# FMC_HPC2.net
KiCad netlist of a schematic drawn in Altium Designer
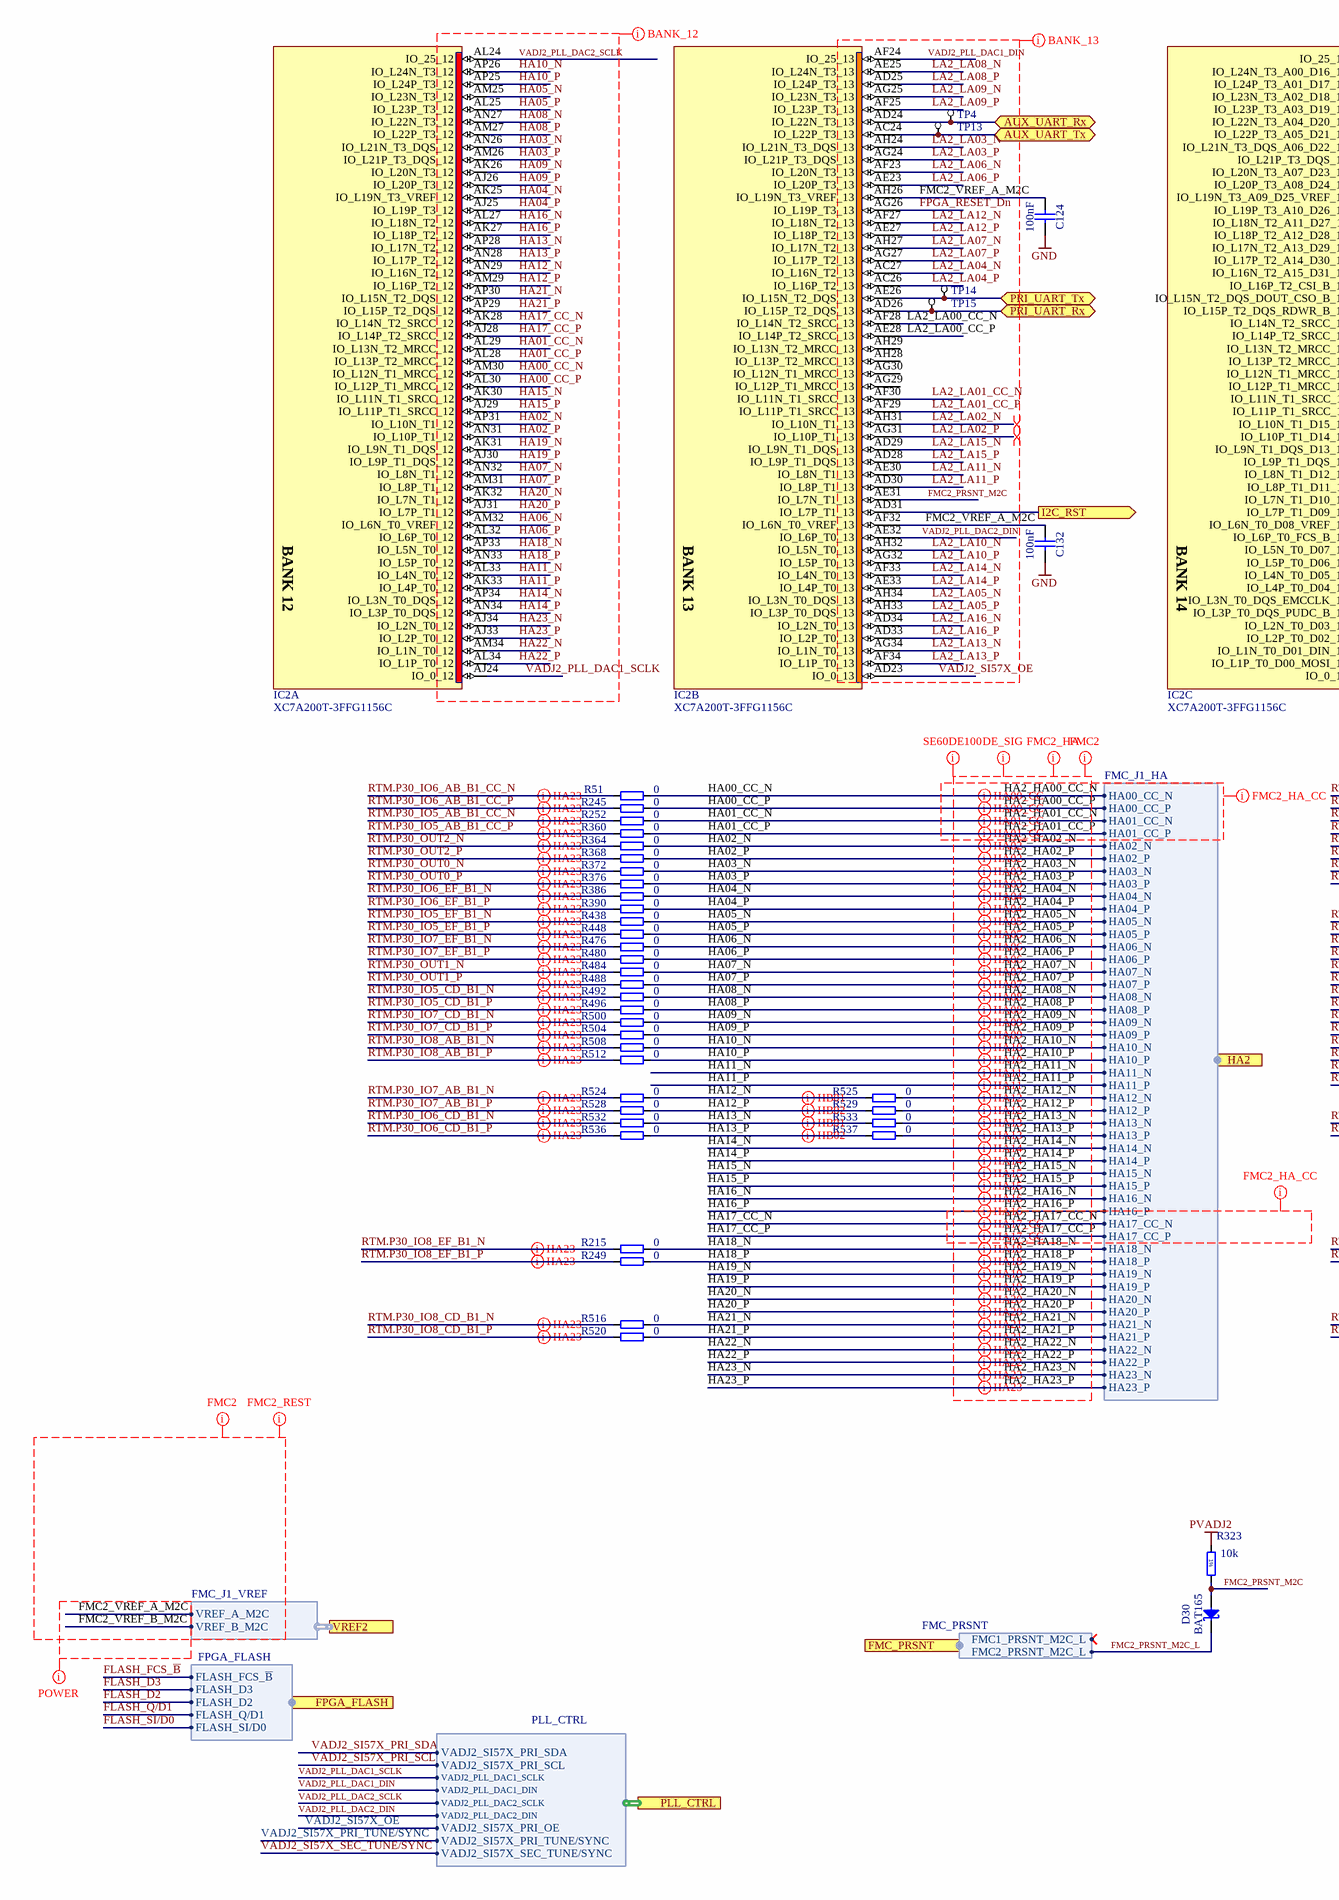
[diagram p0: FMC_HPC2.SchDoc, left]
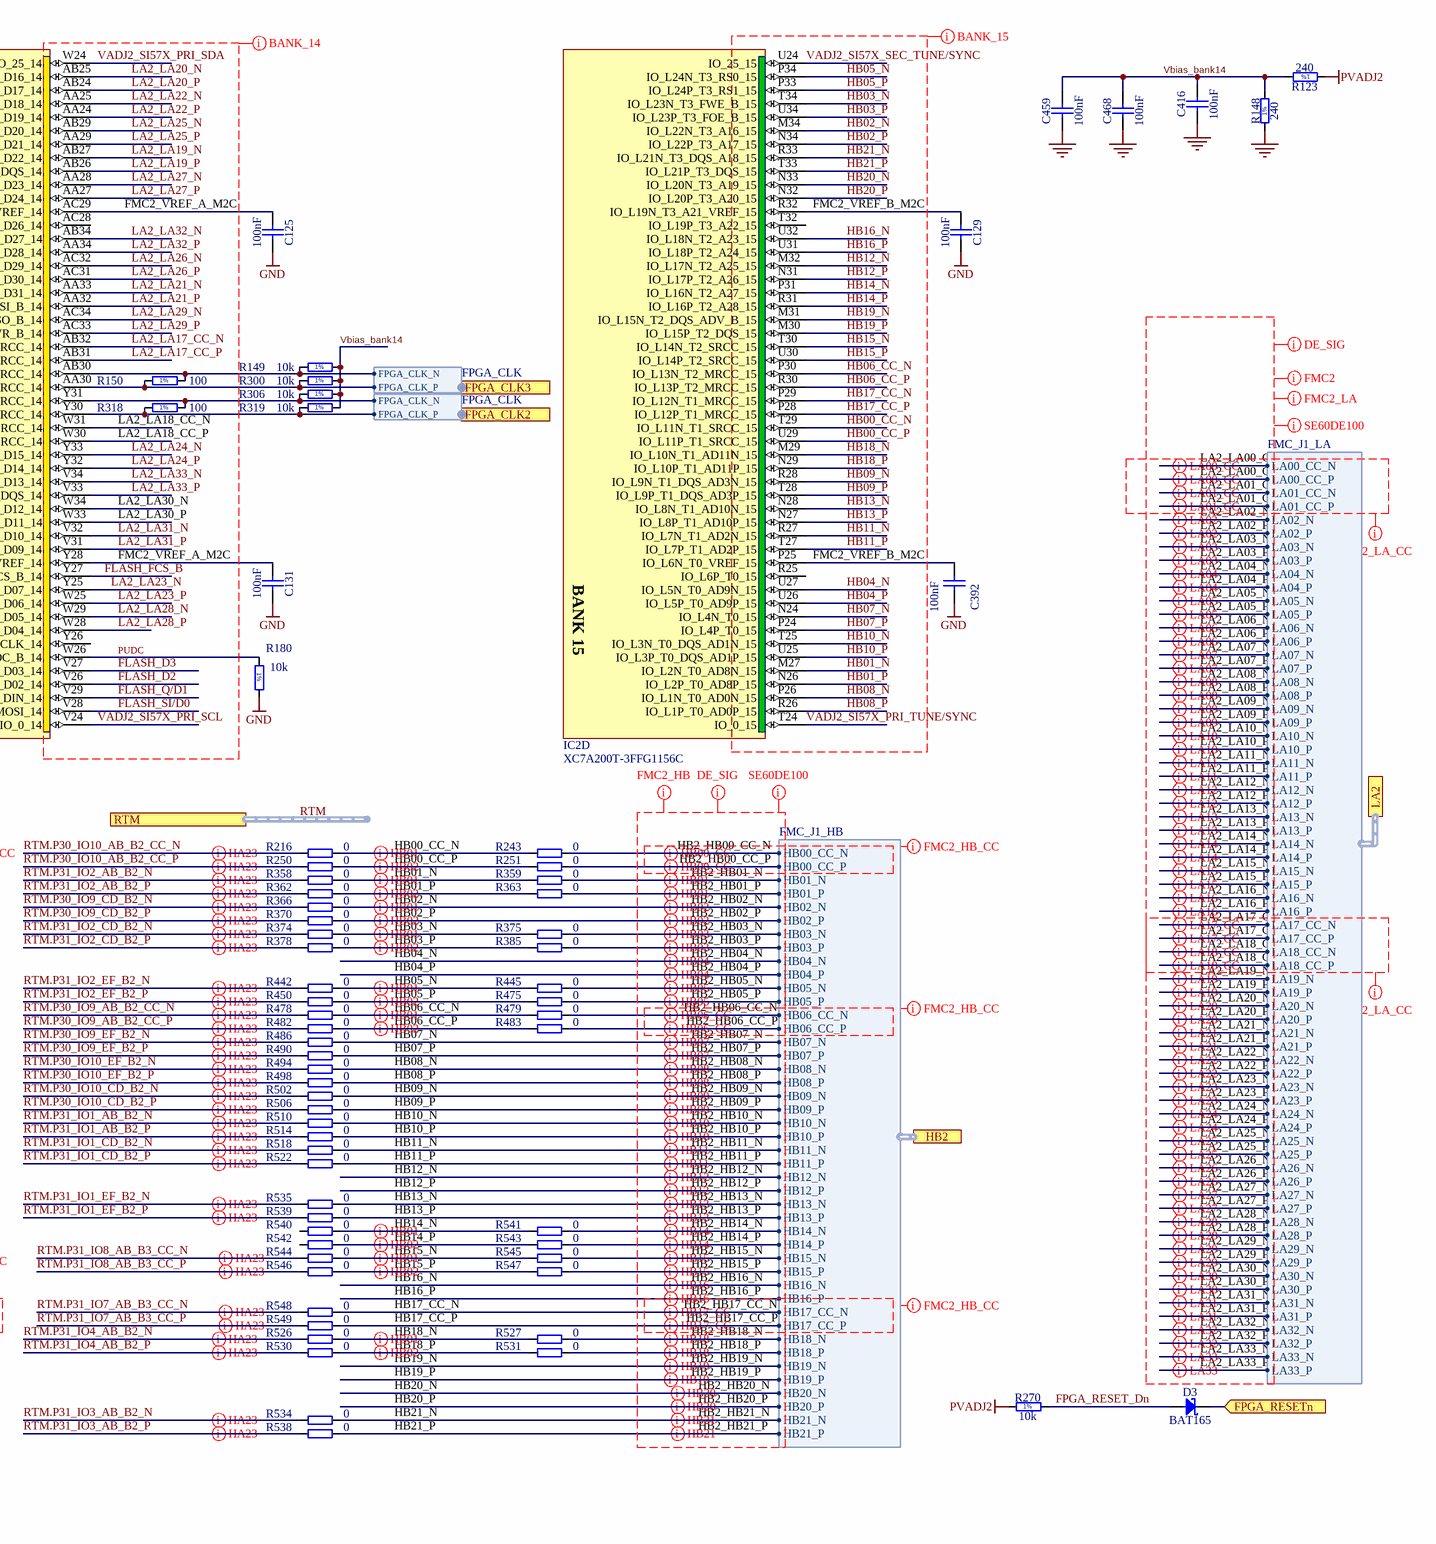
[diagram p1: FMC_HPC2.SchDoc, right]

(export (version "E")
  (design (tool "Eeschema 10.0.6"))
  (components
    (comp (ref "C124")
      (value "100nF")
      (footprint "CAPC0603X33N")
      (description "Non-polarised capacitor")
      (fields
        (field (name "PART NUMBER") "CC0201_100NF_6.3V_10%_X5R")
        (field (name "VOLTAGE") "6.3V")
        (field (name "AUTHOR") "CERN DEM JLC")
      )
      (libsource (lib "Capacitors") (part "Capacitor - non polarized"))
    )
    (comp (ref "C125")
      (value "100nF")
      (footprint "CAPC0603X33N")
      (description "Non-polarised capacitor")
      (fields
        (field (name "PART NUMBER") "CC0201_100NF_6.3V_10%_X5R")
        (field (name "VOLTAGE") "6.3V")
        (field (name "AUTHOR") "CERN DEM JLC")
      )
      (libsource (lib "Capacitors") (part "Capacitor - non polarized"))
    )
    (comp (ref "C129")
      (value "100nF")
      (footprint "CAPC0603X33N")
      (description "Non-polarised capacitor")
      (fields
        (field (name "PART NUMBER") "CC0201_100NF_6.3V_10%_X5R")
        (field (name "VOLTAGE") "6.3V")
        (field (name "AUTHOR") "CERN DEM JLC")
      )
      (libsource (lib "Capacitors") (part "Capacitor - non polarized"))
    )
    (comp (ref "C131")
      (value "100nF")
      (footprint "CAPC0603X33N")
      (description "Non-polarised capacitor")
      (fields
        (field (name "PART NUMBER") "CC0201_100NF_6.3V_10%_X5R")
        (field (name "VOLTAGE") "6.3V")
        (field (name "AUTHOR") "CERN DEM JLC")
      )
      (libsource (lib "Capacitors") (part "Capacitor - non polarized"))
    )
    (comp (ref "C132")
      (value "100nF")
      (footprint "CAPC0603X33N")
      (description "Non-polarised capacitor")
      (fields
        (field (name "PART NUMBER") "CC0201_100NF_6.3V_10%_X5R")
        (field (name "VOLTAGE") "6.3V")
        (field (name "AUTHOR") "CERN DEM JLC")
      )
      (libsource (lib "Capacitors") (part "Capacitor - non polarized"))
    )
    (comp (ref "C392")
      (value "100nF")
      (footprint "CAPC0603X33N")
      (description "Non-polarised capacitor")
      (fields
        (field (name "PART NUMBER") "CC0201_100NF_6.3V_10%_X5R")
        (field (name "VOLTAGE") "6.3V")
        (field (name "AUTHOR") "CERN DEM JLC")
      )
      (libsource (lib "Capacitors") (part "Capacitor - non polarized"))
    )
    (comp (ref "C416")
      (value "100nF")
      (footprint "CAPC0603X33N")
      (description "Non-polarised capacitor")
      (fields
        (field (name "MANUFACTURER PART NUMBER") "CC0201_100NF_6.3V_10%_X5R")
        (field (name "MANUFACTURER") "GENERIC")
        (field (name "AUTHOR") "CERN DEM JLC")
      )
      (libsource (lib "Capacitors") (part "Capacitor - non polarized"))
    )
    (comp (ref "C459")
      (value "100nF")
      (footprint "CAPC0603X33N")
      (description "Non-polarised capacitor")
      (fields
        (field (name "MANUFACTURER PART NUMBER") "CC0201_100NF_6.3V_10%_X5R")
        (field (name "MANUFACTURER") "GENERIC")
        (field (name "AUTHOR") "CERN DEM JLC")
      )
      (libsource (lib "Capacitors") (part "Capacitor - non polarized"))
    )
    (comp (ref "C468")
      (value "100nF")
      (footprint "CAPC0603X33N")
      (description "Non-polarised capacitor")
      (fields
        (field (name "MANUFACTURER PART NUMBER") "CC0201_100NF_6.3V_10%_X5R")
        (field (name "MANUFACTURER") "GENERIC")
        (field (name "AUTHOR") "CERN DEM JLC")
      )
      (libsource (lib "Capacitors") (part "Capacitor - non polarized"))
    )
    (comp (ref "D3")
      (value "BAT165")
      (footprint "SOD2512X110N")
      (description "Schottky Diode")
      (fields
        (field (name "VOLTAGE") "40V")
        (field (name "POWER") "750mA")
        (field (name "AUTHOR") "CERN DEM JLC")
      )
      (libsource (lib "ICs And Semiconductors") (part "Diode Schottky"))
    )
    (comp (ref "D30")
      (value "BAT165")
      (footprint "SOD2512X110N")
      (description "Schottky Diode")
      (fields
        (field (name "MANUFACTURER") "INFINEON")
        (field (name "VOLTAGE") "40V")
        (field (name "AUTHOR") "CERN DEM JLC")
      )
      (libsource (lib "ICs And Semiconductors") (part "Diode Schottky"))
    )
    (comp (ref "IC2")
      (value "XC7A200T-3FFG1156C")
      (footprint "BGA1156C100P34X34_3500X3500X335")
      (description "Artix-6 FPGA, 16 GTPs, 600 User I/Os, 1156-Pin BGA, Speed Grade 2, Commercial Grade, Pb-Free")
      (fields (field (name "MANUFACTURER") "XILINX") (field (name "AUTHOR") "CERN DEM JLC"))
      (libsource (lib "AMC_FMC_Carrier") (part "XC7A200T-3FFG1156C"))
    )
    (comp (ref "R51")
      (value "0")
      (footprint "RESC0603X28N")
      (description "Resistor")
      (fields
        (field (name "PART NUMBER") "R0201_0R_JUMPER")
        (field (name "MANUFACTURER") "GENERIC")
        (field (name "AUTHOR") "CERN DEM JLC")
      )
      (libsource (lib "Resistors") (part "Resistor"))
    )
    (comp (ref "R123")
      (value "240")
      (footprint "RESC1005X40N")
      (description "Resistor - 1%")
      (fields
        (field (name "MANUFACTURER PART NUMBER") "R0402_240R_1%_0.0625W_100PPM")
        (field (name "MANUFACTURER") "GENERIC")
        (field (name "AUTHOR") "CERN DEM JLC")
      )
      (libsource (lib "Resistors") (part "Resistor - 1%"))
    )
    (comp (ref "R148")
      (value "240")
      (footprint "RESC1005X40N")
      (description "Resistor - 1%")
      (fields
        (field (name "MANUFACTURER PART NUMBER") "R0402_240R_1%_0.0625W_100PPM")
        (field (name "MANUFACTURER") "GENERIC")
        (field (name "AUTHOR") "CERN DEM JLC")
      )
      (libsource (lib "Resistors") (part "Resistor - 1%"))
    )
    (comp (ref "R149")
      (value "10k")
      (footprint "RESC1005X40N")
      (description "Resistor - 1%")
      (fields
        (field (name "MANUFACTURER PART NUMBER") "R0402_10K_1%_0.0625W_100PPM")
        (field (name "MANUFACTURER") "GENERIC")
        (field (name "AUTHOR") "CERN DEM JLC")
      )
      (libsource (lib "Resistors") (part "Resistor - 1%"))
    )
    (comp (ref "R150")
      (value "100")
      (footprint "RESC0603X28N")
      (description "Resistor - 1%")
      (fields
        (field (name "MANUFACTURER PART NUMBER") "R0201_100R_1%_0.05W_200PPM")
        (field (name "MANUFACTURER") "GENERIC")
        (field (name "AUTHOR") "CERN DEM JLC")
      )
      (libsource (lib "Resistors") (part "Resistor - 1%"))
    )
    (comp (ref "R180")
      (value "10k")
      (footprint "RESC1005X40N")
      (description "Resistor - 1%")
      (fields
        (field (name "PART NUMBER") "R0402_10K_1%_0.0625W_100PPM")
        (field (name "POWER") "0.0625W")
        (field (name "AUTHOR") "CERN DEM JLC")
      )
      (libsource (lib "Resistors") (part "Resistor - 1%"))
    )
    (comp (ref "R215")
      (value "0")
      (footprint "RESC0603X28N")
      (description "Resistor")
      (fields
        (field (name "PART NUMBER") "R0201_0R_JUMPER")
        (field (name "MANUFACTURER") "GENERIC")
        (field (name "AUTHOR") "CERN DEM JLC")
      )
      (libsource (lib "Resistors") (part "Resistor"))
    )
    (comp (ref "R216")
      (value "0")
      (footprint "RESC0603X28N")
      (description "Resistor")
      (fields
        (field (name "PART NUMBER") "R0201_0R_JUMPER")
        (field (name "MANUFACTURER") "GENERIC")
        (field (name "AUTHOR") "CERN DEM JLC")
      )
      (libsource (lib "Resistors") (part "Resistor"))
    )
    (comp (ref "R243")
      (value "0")
      (footprint "RESC0603X28N")
      (description "Resistor")
      (fields
        (field (name "PART NUMBER") "R0201_0R_JUMPER")
        (field (name "MANUFACTURER") "GENERIC")
        (field (name "AUTHOR") "CERN DEM JLC")
      )
      (libsource (lib "Resistors") (part "Resistor"))
    )
    (comp (ref "R245")
      (value "0")
      (footprint "RESC0603X28N")
      (description "Resistor")
      (fields
        (field (name "PART NUMBER") "R0201_0R_JUMPER")
        (field (name "MANUFACTURER") "GENERIC")
        (field (name "AUTHOR") "CERN DEM JLC")
      )
      (libsource (lib "Resistors") (part "Resistor"))
    )
    (comp (ref "R249")
      (value "0")
      (footprint "RESC0603X28N")
      (description "Resistor")
      (fields
        (field (name "PART NUMBER") "R0201_0R_JUMPER")
        (field (name "MANUFACTURER") "GENERIC")
        (field (name "AUTHOR") "CERN DEM JLC")
      )
      (libsource (lib "Resistors") (part "Resistor"))
    )
    (comp (ref "R250")
      (value "0")
      (footprint "RESC0603X28N")
      (description "Resistor")
      (fields
        (field (name "PART NUMBER") "R0201_0R_JUMPER")
        (field (name "MANUFACTURER") "GENERIC")
        (field (name "AUTHOR") "CERN DEM JLC")
      )
      (libsource (lib "Resistors") (part "Resistor"))
    )
    (comp (ref "R251")
      (value "0")
      (footprint "RESC0603X28N")
      (description "Resistor")
      (fields
        (field (name "PART NUMBER") "R0201_0R_JUMPER")
        (field (name "MANUFACTURER") "GENERIC")
        (field (name "AUTHOR") "CERN DEM JLC")
      )
      (libsource (lib "Resistors") (part "Resistor"))
    )
    (comp (ref "R252")
      (value "0")
      (footprint "RESC0603X28N")
      (description "Resistor")
      (fields
        (field (name "PART NUMBER") "R0201_0R_JUMPER")
        (field (name "MANUFACTURER") "GENERIC")
        (field (name "AUTHOR") "CERN DEM JLC")
      )
      (libsource (lib "Resistors") (part "Resistor"))
    )
    (comp (ref "R270")
      (value "10k")
      (footprint "RESC1005X40N")
      (description "Resistor - 1%")
      (fields
        (field (name "PART NUMBER") "R0402_10K_1%_0.0625W_100PPM")
        (field (name "POWER") "0.0625W")
        (field (name "AUTHOR") "CERN DEM JLC")
      )
      (libsource (lib "Resistors") (part "Resistor - 1%"))
    )
    (comp (ref "R300")
      (value "10k")
      (footprint "RESC1005X40N")
      (description "Resistor - 1%")
      (fields
        (field (name "MANUFACTURER PART NUMBER") "R0402_10K_1%_0.0625W_100PPM")
        (field (name "MANUFACTURER") "GENERIC")
        (field (name "AUTHOR") "CERN DEM JLC")
      )
      (libsource (lib "Resistors") (part "Resistor - 1%"))
    )
    (comp (ref "R306")
      (value "10k")
      (footprint "RESC1005X40N")
      (description "Resistor - 1%")
      (fields
        (field (name "MANUFACTURER PART NUMBER") "R0402_10K_1%_0.0625W_100PPM")
        (field (name "MANUFACTURER") "GENERIC")
        (field (name "AUTHOR") "CERN DEM JLC")
      )
      (libsource (lib "Resistors") (part "Resistor - 1%"))
    )
    (comp (ref "R318")
      (value "100")
      (footprint "RESC0603X28N")
      (description "Resistor - 1%")
      (fields
        (field (name "MANUFACTURER PART NUMBER") "R0201_100R_1%_0.05W_200PPM")
        (field (name "MANUFACTURER") "GENERIC")
        (field (name "AUTHOR") "CERN DEM JLC")
      )
      (libsource (lib "Resistors") (part "Resistor - 1%"))
    )
    (comp (ref "R319")
      (value "10k")
      (footprint "RESC1005X40N")
      (description "Resistor - 1%")
      (fields
        (field (name "MANUFACTURER PART NUMBER") "R0402_10K_1%_0.0625W_100PPM")
        (field (name "MANUFACTURER") "GENERIC")
        (field (name "AUTHOR") "CERN DEM JLC")
      )
      (libsource (lib "Resistors") (part "Resistor - 1%"))
    )
    (comp (ref "R323")
      (value "10k")
      (footprint "RESC1005X40N")
      (description "Resistor - 1%")
      (fields
        (field (name "PART NUMBER") "R0402_10K_1%_0.0625W_100PPM")
        (field (name "POWER") "0.0625W")
        (field (name "AUTHOR") "CERN DEM JLC")
      )
      (libsource (lib "Resistors") (part "Resistor - 1%"))
    )
    (comp (ref "R358")
      (value "0")
      (footprint "RESC0603X28N")
      (description "Resistor")
      (fields
        (field (name "PART NUMBER") "R0201_0R_JUMPER")
        (field (name "MANUFACTURER") "GENERIC")
        (field (name "AUTHOR") "CERN DEM JLC")
      )
      (libsource (lib "Resistors") (part "Resistor"))
    )
    (comp (ref "R359")
      (value "0")
      (footprint "RESC0603X28N")
      (description "Resistor")
      (fields
        (field (name "PART NUMBER") "R0201_0R_JUMPER")
        (field (name "MANUFACTURER") "GENERIC")
        (field (name "AUTHOR") "CERN DEM JLC")
      )
      (libsource (lib "Resistors") (part "Resistor"))
    )
    (comp (ref "R360")
      (value "0")
      (footprint "RESC0603X28N")
      (description "Resistor")
      (fields
        (field (name "PART NUMBER") "R0201_0R_JUMPER")
        (field (name "MANUFACTURER") "GENERIC")
        (field (name "AUTHOR") "CERN DEM JLC")
      )
      (libsource (lib "Resistors") (part "Resistor"))
    )
    (comp (ref "R362")
      (value "0")
      (footprint "RESC0603X28N")
      (description "Resistor")
      (fields
        (field (name "PART NUMBER") "R0201_0R_JUMPER")
        (field (name "MANUFACTURER") "GENERIC")
        (field (name "AUTHOR") "CERN DEM JLC")
      )
      (libsource (lib "Resistors") (part "Resistor"))
    )
    (comp (ref "R363")
      (value "0")
      (footprint "RESC0603X28N")
      (description "Resistor")
      (fields
        (field (name "PART NUMBER") "R0201_0R_JUMPER")
        (field (name "MANUFACTURER") "GENERIC")
        (field (name "AUTHOR") "CERN DEM JLC")
      )
      (libsource (lib "Resistors") (part "Resistor"))
    )
    (comp (ref "R364")
      (value "0")
      (footprint "RESC0603X28N")
      (description "Resistor")
      (fields
        (field (name "PART NUMBER") "R0201_0R_JUMPER")
        (field (name "MANUFACTURER") "GENERIC")
        (field (name "AUTHOR") "CERN DEM JLC")
      )
      (libsource (lib "Resistors") (part "Resistor"))
    )
    (comp (ref "R366")
      (value "0")
      (footprint "RESC0603X28N")
      (description "Resistor")
      (fields
        (field (name "PART NUMBER") "R0201_0R_JUMPER")
        (field (name "MANUFACTURER") "GENERIC")
        (field (name "AUTHOR") "CERN DEM JLC")
      )
      (libsource (lib "Resistors") (part "Resistor"))
    )
    (comp (ref "R368")
      (value "0")
      (footprint "RESC0603X28N")
      (description "Resistor")
      (fields
        (field (name "PART NUMBER") "R0201_0R_JUMPER")
        (field (name "MANUFACTURER") "GENERIC")
        (field (name "AUTHOR") "CERN DEM JLC")
      )
      (libsource (lib "Resistors") (part "Resistor"))
    )
    (comp (ref "R370")
      (value "0")
      (footprint "RESC0603X28N")
      (description "Resistor")
      (fields
        (field (name "PART NUMBER") "R0201_0R_JUMPER")
        (field (name "MANUFACTURER") "GENERIC")
        (field (name "AUTHOR") "CERN DEM JLC")
      )
      (libsource (lib "Resistors") (part "Resistor"))
    )
    (comp (ref "R372")
      (value "0")
      (footprint "RESC0603X28N")
      (description "Resistor")
      (fields
        (field (name "PART NUMBER") "R0201_0R_JUMPER")
        (field (name "MANUFACTURER") "GENERIC")
        (field (name "AUTHOR") "CERN DEM JLC")
      )
      (libsource (lib "Resistors") (part "Resistor"))
    )
    (comp (ref "R374")
      (value "0")
      (footprint "RESC0603X28N")
      (description "Resistor")
      (fields
        (field (name "PART NUMBER") "R0201_0R_JUMPER")
        (field (name "MANUFACTURER") "GENERIC")
        (field (name "AUTHOR") "CERN DEM JLC")
      )
      (libsource (lib "Resistors") (part "Resistor"))
    )
    (comp (ref "R375")
      (value "0")
      (footprint "RESC0603X28N")
      (description "Resistor")
      (fields
        (field (name "PART NUMBER") "R0201_0R_JUMPER")
        (field (name "MANUFACTURER") "GENERIC")
        (field (name "AUTHOR") "CERN DEM JLC")
      )
      (libsource (lib "Resistors") (part "Resistor"))
    )
    (comp (ref "R376")
      (value "0")
      (footprint "RESC0603X28N")
      (description "Resistor")
      (fields
        (field (name "PART NUMBER") "R0201_0R_JUMPER")
        (field (name "MANUFACTURER") "GENERIC")
        (field (name "AUTHOR") "CERN DEM JLC")
      )
      (libsource (lib "Resistors") (part "Resistor"))
    )
    (comp (ref "R378")
      (value "0")
      (footprint "RESC0603X28N")
      (description "Resistor")
      (fields
        (field (name "PART NUMBER") "R0201_0R_JUMPER")
        (field (name "MANUFACTURER") "GENERIC")
        (field (name "AUTHOR") "CERN DEM JLC")
      )
      (libsource (lib "Resistors") (part "Resistor"))
    )
    (comp (ref "R385")
      (value "0")
      (footprint "RESC0603X28N")
      (description "Resistor")
      (fields
        (field (name "PART NUMBER") "R0201_0R_JUMPER")
        (field (name "MANUFACTURER") "GENERIC")
        (field (name "AUTHOR") "CERN DEM JLC")
      )
      (libsource (lib "Resistors") (part "Resistor"))
    )
    (comp (ref "R386")
      (value "0")
      (footprint "RESC0603X28N")
      (description "Resistor")
      (fields
        (field (name "PART NUMBER") "R0201_0R_JUMPER")
        (field (name "MANUFACTURER") "GENERIC")
        (field (name "AUTHOR") "CERN DEM JLC")
      )
      (libsource (lib "Resistors") (part "Resistor"))
    )
    (comp (ref "R390")
      (value "0")
      (footprint "RESC0603X28N")
      (description "Resistor")
      (fields
        (field (name "PART NUMBER") "R0201_0R_JUMPER")
        (field (name "MANUFACTURER") "GENERIC")
        (field (name "AUTHOR") "CERN DEM JLC")
      )
      (libsource (lib "Resistors") (part "Resistor"))
    )
    (comp (ref "R438")
      (value "0")
      (footprint "RESC0603X28N")
      (description "Resistor")
      (fields
        (field (name "PART NUMBER") "R0201_0R_JUMPER")
        (field (name "MANUFACTURER") "GENERIC")
        (field (name "AUTHOR") "CERN DEM JLC")
      )
      (libsource (lib "Resistors") (part "Resistor"))
    )
    (comp (ref "R442")
      (value "0")
      (footprint "RESC0603X28N")
      (description "Resistor")
      (fields
        (field (name "PART NUMBER") "R0201_0R_JUMPER")
        (field (name "MANUFACTURER") "GENERIC")
        (field (name "AUTHOR") "CERN DEM JLC")
      )
      (libsource (lib "Resistors") (part "Resistor"))
    )
    (comp (ref "R445")
      (value "0")
      (footprint "RESC0603X28N")
      (description "Resistor")
      (fields
        (field (name "PART NUMBER") "R0201_0R_JUMPER")
        (field (name "MANUFACTURER") "GENERIC")
        (field (name "AUTHOR") "CERN DEM JLC")
      )
      (libsource (lib "Resistors") (part "Resistor"))
    )
    (comp (ref "R448")
      (value "0")
      (footprint "RESC0603X28N")
      (description "Resistor")
      (fields
        (field (name "PART NUMBER") "R0201_0R_JUMPER")
        (field (name "MANUFACTURER") "GENERIC")
        (field (name "AUTHOR") "CERN DEM JLC")
      )
      (libsource (lib "Resistors") (part "Resistor"))
    )
    (comp (ref "R450")
      (value "0")
      (footprint "RESC0603X28N")
      (description "Resistor")
      (fields
        (field (name "PART NUMBER") "R0201_0R_JUMPER")
        (field (name "MANUFACTURER") "GENERIC")
        (field (name "AUTHOR") "CERN DEM JLC")
      )
      (libsource (lib "Resistors") (part "Resistor"))
    )
    (comp (ref "R475")
      (value "0")
      (footprint "RESC0603X28N")
      (description "Resistor")
      (fields
        (field (name "PART NUMBER") "R0201_0R_JUMPER")
        (field (name "MANUFACTURER") "GENERIC")
        (field (name "AUTHOR") "CERN DEM JLC")
      )
      (libsource (lib "Resistors") (part "Resistor"))
    )
    (comp (ref "R476")
      (value "0")
      (footprint "RESC0603X28N")
      (description "Resistor")
      (fields
        (field (name "PART NUMBER") "R0201_0R_JUMPER")
        (field (name "MANUFACTURER") "GENERIC")
        (field (name "AUTHOR") "CERN DEM JLC")
      )
      (libsource (lib "Resistors") (part "Resistor"))
    )
    (comp (ref "R478")
      (value "0")
      (footprint "RESC0603X28N")
      (description "Resistor")
      (fields
        (field (name "PART NUMBER") "R0201_0R_JUMPER")
        (field (name "MANUFACTURER") "GENERIC")
        (field (name "AUTHOR") "CERN DEM JLC")
      )
      (libsource (lib "Resistors") (part "Resistor"))
    )
    (comp (ref "R479")
      (value "0")
      (footprint "RESC0603X28N")
      (description "Resistor")
      (fields
        (field (name "PART NUMBER") "R0201_0R_JUMPER")
        (field (name "MANUFACTURER") "GENERIC")
        (field (name "AUTHOR") "CERN DEM JLC")
      )
      (libsource (lib "Resistors") (part "Resistor"))
    )
    (comp (ref "R480")
      (value "0")
      (footprint "RESC0603X28N")
      (description "Resistor")
      (fields
        (field (name "PART NUMBER") "R0201_0R_JUMPER")
        (field (name "MANUFACTURER") "GENERIC")
        (field (name "AUTHOR") "CERN DEM JLC")
      )
      (libsource (lib "Resistors") (part "Resistor"))
    )
    (comp (ref "R482")
      (value "0")
      (footprint "RESC0603X28N")
      (description "Resistor")
      (fields
        (field (name "PART NUMBER") "R0201_0R_JUMPER")
        (field (name "MANUFACTURER") "GENERIC")
        (field (name "AUTHOR") "CERN DEM JLC")
      )
      (libsource (lib "Resistors") (part "Resistor"))
    )
    (comp (ref "R483")
      (value "0")
      (footprint "RESC0603X28N")
      (description "Resistor")
      (fields
        (field (name "PART NUMBER") "R0201_0R_JUMPER")
        (field (name "MANUFACTURER") "GENERIC")
        (field (name "AUTHOR") "CERN DEM JLC")
      )
      (libsource (lib "Resistors") (part "Resistor"))
    )
    (comp (ref "R484")
      (value "0")
      (footprint "RESC0603X28N")
      (description "Resistor")
      (fields
        (field (name "PART NUMBER") "R0201_0R_JUMPER")
        (field (name "MANUFACTURER") "GENERIC")
        (field (name "AUTHOR") "CERN DEM JLC")
      )
      (libsource (lib "Resistors") (part "Resistor"))
    )
    (comp (ref "R486")
      (value "0")
      (footprint "RESC0603X28N")
      (description "Resistor")
      (fields
        (field (name "PART NUMBER") "R0201_0R_JUMPER")
        (field (name "MANUFACTURER") "GENERIC")
        (field (name "AUTHOR") "CERN DEM JLC")
      )
      (libsource (lib "Resistors") (part "Resistor"))
    )
    (comp (ref "R488")
      (value "0")
      (footprint "RESC0603X28N")
      (description "Resistor")
      (fields
        (field (name "PART NUMBER") "R0201_0R_JUMPER")
        (field (name "MANUFACTURER") "GENERIC")
        (field (name "AUTHOR") "CERN DEM JLC")
      )
      (libsource (lib "Resistors") (part "Resistor"))
    )
    (comp (ref "R490")
      (value "0")
      (footprint "RESC0603X28N")
      (description "Resistor")
      (fields
        (field (name "PART NUMBER") "R0201_0R_JUMPER")
        (field (name "MANUFACTURER") "GENERIC")
        (field (name "AUTHOR") "CERN DEM JLC")
      )
      (libsource (lib "Resistors") (part "Resistor"))
    )
    (comp (ref "R492")
      (value "0")
      (footprint "RESC0603X28N")
      (description "Resistor")
      (fields
        (field (name "PART NUMBER") "R0201_0R_JUMPER")
        (field (name "MANUFACTURER") "GENERIC")
        (field (name "AUTHOR") "CERN DEM JLC")
      )
      (libsource (lib "Resistors") (part "Resistor"))
    )
    (comp (ref "R494")
      (value "0")
      (footprint "RESC0603X28N")
      (description "Resistor")
      (fields
        (field (name "PART NUMBER") "R0201_0R_JUMPER")
        (field (name "MANUFACTURER") "GENERIC")
        (field (name "AUTHOR") "CERN DEM JLC")
      )
      (libsource (lib "Resistors") (part "Resistor"))
    )
    (comp (ref "R496")
      (value "0")
      (footprint "RESC0603X28N")
      (description "Resistor")
      (fields
        (field (name "PART NUMBER") "R0201_0R_JUMPER")
        (field (name "MANUFACTURER") "GENERIC")
        (field (name "AUTHOR") "CERN DEM JLC")
      )
      (libsource (lib "Resistors") (part "Resistor"))
    )
    (comp (ref "R498")
      (value "0")
      (footprint "RESC0603X28N")
      (description "Resistor")
      (fields
        (field (name "PART NUMBER") "R0201_0R_JUMPER")
        (field (name "MANUFACTURER") "GENERIC")
        (field (name "AUTHOR") "CERN DEM JLC")
      )
      (libsource (lib "Resistors") (part "Resistor"))
    )
    (comp (ref "R500")
      (value "0")
      (footprint "RESC0603X28N")
      (description "Resistor")
      (fields
        (field (name "PART NUMBER") "R0201_0R_JUMPER")
        (field (name "MANUFACTURER") "GENERIC")
        (field (name "AUTHOR") "CERN DEM JLC")
      )
      (libsource (lib "Resistors") (part "Resistor"))
    )
    (comp (ref "R502")
      (value "0")
      (footprint "RESC0603X28N")
      (description "Resistor")
      (fields
        (field (name "PART NUMBER") "R0201_0R_JUMPER")
        (field (name "MANUFACTURER") "GENERIC")
        (field (name "AUTHOR") "CERN DEM JLC")
      )
      (libsource (lib "Resistors") (part "Resistor"))
    )
    (comp (ref "R504")
      (value "0")
      (footprint "RESC0603X28N")
      (description "Resistor")
      (fields
        (field (name "PART NUMBER") "R0201_0R_JUMPER")
        (field (name "MANUFACTURER") "GENERIC")
        (field (name "AUTHOR") "CERN DEM JLC")
      )
      (libsource (lib "Resistors") (part "Resistor"))
    )
    (comp (ref "R506")
      (value "0")
      (footprint "RESC0603X28N")
      (description "Resistor")
      (fields
        (field (name "PART NUMBER") "R0201_0R_JUMPER")
        (field (name "MANUFACTURER") "GENERIC")
        (field (name "AUTHOR") "CERN DEM JLC")
      )
      (libsource (lib "Resistors") (part "Resistor"))
    )
    (comp (ref "R508")
      (value "0")
      (footprint "RESC0603X28N")
      (description "Resistor")
      (fields
        (field (name "PART NUMBER") "R0201_0R_JUMPER")
        (field (name "MANUFACTURER") "GENERIC")
        (field (name "AUTHOR") "CERN DEM JLC")
      )
      (libsource (lib "Resistors") (part "Resistor"))
    )
    (comp (ref "R510")
      (value "0")
      (footprint "RESC0603X28N")
      (description "Resistor")
      (fields
        (field (name "PART NUMBER") "R0201_0R_JUMPER")
        (field (name "MANUFACTURER") "GENERIC")
        (field (name "AUTHOR") "CERN DEM JLC")
      )
      (libsource (lib "Resistors") (part "Resistor"))
    )
    (comp (ref "R512")
      (value "0")
      (footprint "RESC0603X28N")
      (description "Resistor")
      (fields
        (field (name "PART NUMBER") "R0201_0R_JUMPER")
        (field (name "MANUFACTURER") "GENERIC")
        (field (name "AUTHOR") "CERN DEM JLC")
      )
      (libsource (lib "Resistors") (part "Resistor"))
    )
    (comp (ref "R514")
      (value "0")
      (footprint "RESC0603X28N")
      (description "Resistor")
      (fields
        (field (name "PART NUMBER") "R0201_0R_JUMPER")
        (field (name "MANUFACTURER") "GENERIC")
        (field (name "AUTHOR") "CERN DEM JLC")
      )
      (libsource (lib "Resistors") (part "Resistor"))
    )
    (comp (ref "R516")
      (value "0")
      (footprint "RESC0603X28N")
      (description "Resistor")
      (fields
        (field (name "PART NUMBER") "R0201_0R_JUMPER")
        (field (name "MANUFACTURER") "GENERIC")
        (field (name "AUTHOR") "CERN DEM JLC")
      )
      (libsource (lib "Resistors") (part "Resistor"))
    )
    (comp (ref "R518")
      (value "0")
      (footprint "RESC0603X28N")
      (description "Resistor")
      (fields
        (field (name "PART NUMBER") "R0201_0R_JUMPER")
        (field (name "MANUFACTURER") "GENERIC")
        (field (name "AUTHOR") "CERN DEM JLC")
      )
      (libsource (lib "Resistors") (part "Resistor"))
    )
    (comp (ref "R520")
      (value "0")
      (footprint "RESC0603X28N")
      (description "Resistor")
      (fields
        (field (name "PART NUMBER") "R0201_0R_JUMPER")
        (field (name "MANUFACTURER") "GENERIC")
        (field (name "AUTHOR") "CERN DEM JLC")
      )
      (libsource (lib "Resistors") (part "Resistor"))
    )
    (comp (ref "R522")
      (value "0")
      (footprint "RESC0603X28N")
      (description "Resistor")
      (fields
        (field (name "PART NUMBER") "R0201_0R_JUMPER")
        (field (name "MANUFACTURER") "GENERIC")
        (field (name "AUTHOR") "CERN DEM JLC")
      )
      (libsource (lib "Resistors") (part "Resistor"))
    )
    (comp (ref "R524")
      (value "0")
      (footprint "RESC0603X28N")
      (description "Resistor")
      (fields
        (field (name "PART NUMBER") "R0201_0R_JUMPER")
        (field (name "MANUFACTURER") "GENERIC")
        (field (name "AUTHOR") "CERN DEM JLC")
      )
      (libsource (lib "Resistors") (part "Resistor"))
    )
    (comp (ref "R525")
      (value "0")
      (footprint "RESC0603X28N")
      (description "Resistor")
      (fields
        (field (name "PART NUMBER") "R0201_0R_JUMPER")
        (field (name "MANUFACTURER") "GENERIC")
        (field (name "AUTHOR") "CERN DEM JLC")
      )
      (libsource (lib "Resistors") (part "Resistor"))
    )
    (comp (ref "R526")
      (value "0")
      (footprint "RESC0603X28N")
      (description "Resistor")
      (fields
        (field (name "PART NUMBER") "R0201_0R_JUMPER")
        (field (name "MANUFACTURER") "GENERIC")
        (field (name "AUTHOR") "CERN DEM JLC")
      )
      (libsource (lib "Resistors") (part "Resistor"))
    )
    (comp (ref "R527")
      (value "0")
      (footprint "RESC0603X28N")
      (description "Resistor")
      (fields
        (field (name "PART NUMBER") "R0201_0R_JUMPER")
        (field (name "MANUFACTURER") "GENERIC")
        (field (name "AUTHOR") "CERN DEM JLC")
      )
      (libsource (lib "Resistors") (part "Resistor"))
    )
    (comp (ref "R528")
      (value "0")
      (footprint "RESC0603X28N")
      (description "Resistor")
      (fields
        (field (name "PART NUMBER") "R0201_0R_JUMPER")
        (field (name "MANUFACTURER") "GENERIC")
        (field (name "AUTHOR") "CERN DEM JLC")
      )
      (libsource (lib "Resistors") (part "Resistor"))
    )
    (comp (ref "R529")
      (value "0")
      (footprint "RESC0603X28N")
      (description "Resistor")
      (fields
        (field (name "PART NUMBER") "R0201_0R_JUMPER")
        (field (name "MANUFACTURER") "GENERIC")
        (field (name "AUTHOR") "CERN DEM JLC")
      )
      (libsource (lib "Resistors") (part "Resistor"))
    )
    (comp (ref "R530")
      (value "0")
      (footprint "RESC0603X28N")
      (description "Resistor")
      (fields
        (field (name "PART NUMBER") "R0201_0R_JUMPER")
        (field (name "MANUFACTURER") "GENERIC")
        (field (name "AUTHOR") "CERN DEM JLC")
      )
      (libsource (lib "Resistors") (part "Resistor"))
    )
    (comp (ref "R531")
      (value "0")
      (footprint "RESC0603X28N")
      (description "Resistor")
      (fields
        (field (name "PART NUMBER") "R0201_0R_JUMPER")
        (field (name "MANUFACTURER") "GENERIC")
        (field (name "AUTHOR") "CERN DEM JLC")
      )
      (libsource (lib "Resistors") (part "Resistor"))
    )
    (comp (ref "R532")
      (value "0")
      (footprint "RESC0603X28N")
      (description "Resistor")
      (fields
        (field (name "PART NUMBER") "R0201_0R_JUMPER")
        (field (name "MANUFACTURER") "GENERIC")
        (field (name "AUTHOR") "CERN DEM JLC")
      )
      (libsource (lib "Resistors") (part "Resistor"))
    )
    (comp (ref "R533")
      (value "0")
      (footprint "RESC0603X28N")
      (description "Resistor")
      (fields
        (field (name "PART NUMBER") "R0201_0R_JUMPER")
        (field (name "MANUFACTURER") "GENERIC")
        (field (name "AUTHOR") "CERN DEM JLC")
      )
      (libsource (lib "Resistors") (part "Resistor"))
    )
    (comp (ref "R534")
      (value "0")
      (footprint "RESC0603X28N")
      (description "Resistor")
      (fields
        (field (name "PART NUMBER") "R0201_0R_JUMPER")
        (field (name "MANUFACTURER") "GENERIC")
        (field (name "AUTHOR") "CERN DEM JLC")
      )
      (libsource (lib "Resistors") (part "Resistor"))
    )
    (comp (ref "R535")
      (value "0")
      (footprint "RESC0603X28N")
      (description "Resistor")
      (fields
        (field (name "PART NUMBER") "R0201_0R_JUMPER")
        (field (name "MANUFACTURER") "GENERIC")
        (field (name "AUTHOR") "CERN DEM JLC")
      )
      (libsource (lib "Resistors") (part "Resistor"))
    )
    (comp (ref "R536")
      (value "0")
      (footprint "RESC0603X28N")
      (description "Resistor")
      (fields
        (field (name "PART NUMBER") "R0201_0R_JUMPER")
        (field (name "MANUFACTURER") "GENERIC")
        (field (name "AUTHOR") "CERN DEM JLC")
      )
      (libsource (lib "Resistors") (part "Resistor"))
    )
    (comp (ref "R537")
      (value "0")
      (footprint "RESC0603X28N")
      (description "Resistor")
      (fields
        (field (name "PART NUMBER") "R0201_0R_JUMPER")
        (field (name "MANUFACTURER") "GENERIC")
        (field (name "AUTHOR") "CERN DEM JLC")
      )
      (libsource (lib "Resistors") (part "Resistor"))
    )
    (comp (ref "R538")
      (value "0")
      (footprint "RESC0603X28N")
      (description "Resistor")
      (fields
        (field (name "PART NUMBER") "R0201_0R_JUMPER")
        (field (name "MANUFACTURER") "GENERIC")
        (field (name "AUTHOR") "CERN DEM JLC")
      )
      (libsource (lib "Resistors") (part "Resistor"))
    )
    (comp (ref "R539")
      (value "0")
      (footprint "RESC0603X28N")
      (description "Resistor")
      (fields
        (field (name "PART NUMBER") "R0201_0R_JUMPER")
        (field (name "MANUFACTURER") "GENERIC")
        (field (name "AUTHOR") "CERN DEM JLC")
      )
      (libsource (lib "Resistors") (part "Resistor"))
    )
    (comp (ref "R540")
      (value "0")
      (footprint "RESC0603X28N")
      (description "Resistor")
      (fields
        (field (name "PART NUMBER") "R0201_0R_JUMPER")
        (field (name "MANUFACTURER") "GENERIC")
        (field (name "AUTHOR") "CERN DEM JLC")
      )
      (libsource (lib "Resistors") (part "Resistor"))
    )
    (comp (ref "R541")
      (value "0")
      (footprint "RESC0603X28N")
      (description "Resistor")
      (fields
        (field (name "PART NUMBER") "R0201_0R_JUMPER")
        (field (name "MANUFACTURER") "GENERIC")
        (field (name "AUTHOR") "CERN DEM JLC")
      )
      (libsource (lib "Resistors") (part "Resistor"))
    )
    (comp (ref "R542")
      (value "0")
      (footprint "RESC0603X28N")
      (description "Resistor")
      (fields
        (field (name "PART NUMBER") "R0201_0R_JUMPER")
        (field (name "MANUFACTURER") "GENERIC")
        (field (name "AUTHOR") "CERN DEM JLC")
      )
      (libsource (lib "Resistors") (part "Resistor"))
    )
    (comp (ref "R543")
      (value "0")
      (footprint "RESC0603X28N")
      (description "Resistor")
      (fields
        (field (name "PART NUMBER") "R0201_0R_JUMPER")
        (field (name "MANUFACTURER") "GENERIC")
        (field (name "AUTHOR") "CERN DEM JLC")
      )
      (libsource (lib "Resistors") (part "Resistor"))
    )
    (comp (ref "R544")
      (value "0")
      (footprint "RESC0603X28N")
      (description "Resistor")
      (fields
        (field (name "PART NUMBER") "R0201_0R_JUMPER")
        (field (name "MANUFACTURER") "GENERIC")
        (field (name "AUTHOR") "CERN DEM JLC")
      )
      (libsource (lib "Resistors") (part "Resistor"))
    )
    (comp (ref "R545")
      (value "0")
      (footprint "RESC0603X28N")
      (description "Resistor")
      (fields
        (field (name "PART NUMBER") "R0201_0R_JUMPER")
        (field (name "MANUFACTURER") "GENERIC")
        (field (name "AUTHOR") "CERN DEM JLC")
      )
      (libsource (lib "Resistors") (part "Resistor"))
    )
    (comp (ref "R546")
      (value "0")
      (footprint "RESC0603X28N")
      (description "Resistor")
      (fields
        (field (name "PART NUMBER") "R0201_0R_JUMPER")
        (field (name "MANUFACTURER") "GENERIC")
        (field (name "AUTHOR") "CERN DEM JLC")
      )
      (libsource (lib "Resistors") (part "Resistor"))
    )
    (comp (ref "R547")
      (value "0")
      (footprint "RESC0603X28N")
      (description "Resistor")
      (fields
        (field (name "PART NUMBER") "R0201_0R_JUMPER")
        (field (name "MANUFACTURER") "GENERIC")
        (field (name "AUTHOR") "CERN DEM JLC")
      )
      (libsource (lib "Resistors") (part "Resistor"))
    )
    (comp (ref "R548")
      (value "0")
      (footprint "RESC0603X28N")
      (description "Resistor")
      (fields
        (field (name "PART NUMBER") "R0201_0R_JUMPER")
        (field (name "MANUFACTURER") "GENERIC")
        (field (name "AUTHOR") "CERN DEM JLC")
      )
      (libsource (lib "Resistors") (part "Resistor"))
    )
    (comp (ref "R549")
      (value "0")
      (footprint "RESC0603X28N")
      (description "Resistor")
      (fields
        (field (name "PART NUMBER") "R0201_0R_JUMPER")
        (field (name "MANUFACTURER") "GENERIC")
        (field (name "AUTHOR") "CERN DEM JLC")
      )
      (libsource (lib "Resistors") (part "Resistor"))
    )
    (comp (ref "TP4")
      (value "TP")
      (footprint "TP_large")
      (description "Testpoint")
      (libsource (lib "LIBRARY_SCH") (part "TP"))
    )
    (comp (ref "TP13")
      (value "TP")
      (footprint "TP_large")
      (description "Testpoint")
      (libsource (lib "LIBRARY_SCH") (part "TP"))
    )
    (comp (ref "TP14")
      (value "TP")
      (footprint "TP_large")
      (description "Testpoint")
      (libsource (lib "LIBRARY_SCH") (part "TP"))
    )
    (comp (ref "TP15")
      (value "TP")
      (footprint "TP_large")
      (description "Testpoint")
      (libsource (lib "LIBRARY_SCH") (part "TP"))
    )
  )
  (nets
    (net (code "11") (name "/AUX_UART_Rx") (class "Default")
      (node (ref "IC2") (pin "AD24") (pinfunction "IO_L22N_T3_13_AD24") (pintype "bidirectional"))
      (node (ref "TP4") (pin "1") (pintype "passive"))
    )
    (net (code "12") (name "/AUX_UART_Tx") (class "Default")
      (node (ref "IC2") (pin "AC24") (pinfunction "IO_L22P_T3_13_AC24") (pintype "bidirectional"))
      (node (ref "TP13") (pin "1") (pintype "passive"))
    )
    (net (code "13") (name "/FLASH_D2") (class "Default")
      (node (ref "IC2") (pin "V26") (pinfunction "IO_L2P_T0_D02_14_V26") (pintype "bidirectional"))
    )
    (net (code "14") (name "/FLASH_D3") (class "Default")
      (node (ref "IC2") (pin "V27") (pinfunction "IO_L2N_T0_D03_14_V27") (pintype "bidirectional"))
    )
    (net (code "15") (name "/FLASH_FCS_~{B}") (class "Default")
      (node (ref "IC2") (pin "Y27") (pinfunction "IO_L6P_T0_FCS_B_14_Y27") (pintype "bidirectional"))
    )
    (net (code "16") (name "/FLASH_Q{slash}D1") (class "Default")
      (node (ref "IC2") (pin "V29") (pinfunction "IO_L1N_T0_D01_DIN_14_V29") (pintype "bidirectional"))
    )
    (net (code "17") (name "/FLASH_SI{slash}D0") (class "Default")
      (node (ref "IC2") (pin "V28") (pinfunction "IO_L1P_T0_D00_MOSI_14_V28") (pintype "bidirectional"))
    )
    (net (code "18") (name "/FMC2_PRSNT_M2C") (class "Default")
      (node (ref "D30") (pin "2") (pinfunction "A_2") (pintype "passive"))
      (node (ref "IC2") (pin "AE31") (pinfunction "IO_L7N_T1_13_AE31") (pintype "bidirectional"))
      (node (ref "R323") (pin "2") (pinfunction "2_2") (pintype "passive"))
    )
    (net (code "19") (name "/FMC2_PRSNT_M2C_L") (class "Default")
      (node (ref "D30") (pin "1") (pinfunction "C_1") (pintype "passive"))
    )
    (net (code "20") (name "/FMC2_VREF_A_M2C") (class "Default")
      (node (ref "C124") (pin "1") (pinfunction "1_1") (pintype "passive"))
      (node (ref "C125") (pin "1") (pinfunction "1_1") (pintype "passive"))
      (node (ref "C131") (pin "1") (pinfunction "1_1") (pintype "passive"))
      (node (ref "C132") (pin "1") (pinfunction "1_1") (pintype "passive"))
      (node (ref "IC2") (pin "AC29") (pinfunction "IO_L19N_T3_A09_D25_VREF_14_AC29") (pintype "bidirectional"))
      (node (ref "IC2") (pin "AF32") (pinfunction "IO_L6N_T0_VREF_13_AF32") (pintype "bidirectional"))
      (node (ref "IC2") (pin "AH26") (pinfunction "IO_L19N_T3_VREF_13_AH26") (pintype "bidirectional"))
      (node (ref "IC2") (pin "Y28") (pinfunction "IO_L6N_T0_D08_VREF_14_Y28") (pintype "bidirectional"))
    )
    (net (code "21") (name "/FMC2_VREF_B_M2C") (class "Default")
      (node (ref "C129") (pin "1") (pinfunction "1_1") (pintype "passive"))
      (node (ref "C392") (pin "1") (pinfunction "1_1") (pintype "passive"))
      (node (ref "IC2") (pin "P25") (pinfunction "IO_L6N_T0_VREF_15_P25") (pintype "bidirectional"))
      (node (ref "IC2") (pin "R32") (pinfunction "IO_L19N_T3_A21_VREF_15_R32") (pintype "bidirectional"))
    )
    (net (code "23") (name "/FPGA_RESET_Dn") (class "Default")
      (node (ref "D3") (pin "2") (pinfunction "A_2") (pintype "passive"))
      (node (ref "IC2") (pin "AG26") (pinfunction "IO_L19P_T3_13_AG26") (pintype "bidirectional"))
      (node (ref "R270") (pin "2") (pinfunction "2_2") (pintype "passive"))
    )
    (net (code "24") (name "/FPGA_RESETn") (class "Default")
      (node (ref "D3") (pin "1") (pinfunction "C_1") (pintype "passive"))
    )
    (net (code "25") (name "/HA00_CC_N") (class "Default")
      (node (ref "IC2") (pin "AM30") (pinfunction "IO_L12N_T1_MRCC_12_AM30") (pintype "bidirectional"))
      (node (ref "R51") (pin "2") (pinfunction "2_2") (pintype "passive"))
    )
    (net (code "26") (name "/HA00_CC_P") (class "Default")
      (node (ref "IC2") (pin "AL30") (pinfunction "IO_L12P_T1_MRCC_12_AL30") (pintype "bidirectional"))
      (node (ref "R245") (pin "2") (pinfunction "2_2") (pintype "passive"))
    )
    (net (code "27") (name "/HA01_CC_N") (class "Default")
      (node (ref "IC2") (pin "AL29") (pinfunction "IO_L13N_T2_MRCC_12_AL29") (pintype "bidirectional"))
      (node (ref "R252") (pin "2") (pinfunction "2_2") (pintype "passive"))
    )
    (net (code "28") (name "/HA01_CC_P") (class "Default")
      (node (ref "IC2") (pin "AL28") (pinfunction "IO_L13P_T2_MRCC_12_AL28") (pintype "bidirectional"))
      (node (ref "R360") (pin "2") (pinfunction "2_2") (pintype "passive"))
    )
    (net (code "29") (name "/HA2_HA12_N") (class "Default")
      (node (ref "R525") (pin "2") (pinfunction "2_2") (pintype "passive"))
    )
    (net (code "30") (name "/HA2_HA12_P") (class "Default")
      (node (ref "R529") (pin "2") (pinfunction "2_2") (pintype "passive"))
    )
    (net (code "31") (name "/HA2_HA13_N") (class "Default")
      (node (ref "R533") (pin "2") (pinfunction "2_2") (pintype "passive"))
    )
    (net (code "32") (name "/HA2_HA13_P") (class "Default")
      (node (ref "R537") (pin "2") (pinfunction "2_2") (pintype "passive"))
    )
    (net (code "33") (name "/HA02_N") (class "Default")
      (node (ref "IC2") (pin "AP31") (pinfunction "IO_L10N_T1_12_AP31") (pintype "bidirectional"))
      (node (ref "R364") (pin "2") (pinfunction "2_2") (pintype "passive"))
    )
    (net (code "34") (name "/HA02_P") (class "Default")
      (node (ref "IC2") (pin "AN31") (pinfunction "IO_L10P_T1_12_AN31") (pintype "bidirectional"))
      (node (ref "R368") (pin "2") (pinfunction "2_2") (pintype "passive"))
    )
    (net (code "35") (name "/HA03_N") (class "Default")
      (node (ref "IC2") (pin "AN26") (pinfunction "IO_L21N_T3_DQS_12_AN26") (pintype "bidirectional"))
      (node (ref "R372") (pin "2") (pinfunction "2_2") (pintype "passive"))
    )
    (net (code "36") (name "/HA03_P") (class "Default")
      (node (ref "IC2") (pin "AM26") (pinfunction "IO_L21P_T3_DQS_12_AM26") (pintype "bidirectional"))
      (node (ref "R376") (pin "2") (pinfunction "2_2") (pintype "passive"))
    )
    (net (code "37") (name "/HA04_N") (class "Default")
      (node (ref "IC2") (pin "AK25") (pinfunction "IO_L19N_T3_VREF_12_AK25") (pintype "bidirectional"))
      (node (ref "R386") (pin "2") (pinfunction "2_2") (pintype "passive"))
    )
    (net (code "38") (name "/HA04_P") (class "Default")
      (node (ref "IC2") (pin "AJ25") (pinfunction "IO_L19P_T3_12_AJ25") (pintype "bidirectional"))
      (node (ref "R390") (pin "2") (pinfunction "2_2") (pintype "passive"))
    )
    (net (code "39") (name "/HA05_N") (class "Default")
      (node (ref "IC2") (pin "AM25") (pinfunction "IO_L23N_T3_12_AM25") (pintype "bidirectional"))
      (node (ref "R438") (pin "2") (pinfunction "2_2") (pintype "passive"))
    )
    (net (code "40") (name "/HA05_P") (class "Default")
      (node (ref "IC2") (pin "AL25") (pinfunction "IO_L23P_T3_12_AL25") (pintype "bidirectional"))
      (node (ref "R448") (pin "2") (pinfunction "2_2") (pintype "passive"))
    )
    (net (code "41") (name "/HA06_N") (class "Default")
      (node (ref "IC2") (pin "AM32") (pinfunction "IO_L6N_T0_VREF_12_AM32") (pintype "bidirectional"))
      (node (ref "R476") (pin "2") (pinfunction "2_2") (pintype "passive"))
    )
    (net (code "42") (name "/HA06_P") (class "Default")
      (node (ref "IC2") (pin "AL32") (pinfunction "IO_L6P_T0_12_AL32") (pintype "bidirectional"))
      (node (ref "R480") (pin "2") (pinfunction "2_2") (pintype "passive"))
    )
    (net (code "43") (name "/HA07_N") (class "Default")
      (node (ref "IC2") (pin "AN32") (pinfunction "IO_L8N_T1_12_AN32") (pintype "bidirectional"))
      (node (ref "R484") (pin "2") (pinfunction "2_2") (pintype "passive"))
    )
    (net (code "44") (name "/HA07_P") (class "Default")
      (node (ref "IC2") (pin "AM31") (pinfunction "IO_L8P_T1_12_AM31") (pintype "bidirectional"))
      (node (ref "R488") (pin "2") (pinfunction "2_2") (pintype "passive"))
    )
    (net (code "45") (name "/HA08_N") (class "Default")
      (node (ref "IC2") (pin "AN27") (pinfunction "IO_L22N_T3_12_AN27") (pintype "bidirectional"))
      (node (ref "R492") (pin "2") (pinfunction "2_2") (pintype "passive"))
    )
    (net (code "46") (name "/HA08_P") (class "Default")
      (node (ref "IC2") (pin "AM27") (pinfunction "IO_L22P_T3_12_AM27") (pintype "bidirectional"))
      (node (ref "R496") (pin "2") (pinfunction "2_2") (pintype "passive"))
    )
    (net (code "47") (name "/HA09_N") (class "Default")
      (node (ref "IC2") (pin "AK26") (pinfunction "IO_L20N_T3_12_AK26") (pintype "bidirectional"))
      (node (ref "R500") (pin "2") (pinfunction "2_2") (pintype "passive"))
    )
    (net (code "48") (name "/HA09_P") (class "Default")
      (node (ref "IC2") (pin "AJ26") (pinfunction "IO_L20P_T3_12_AJ26") (pintype "bidirectional"))
      (node (ref "R504") (pin "2") (pinfunction "2_2") (pintype "passive"))
    )
    (net (code "49") (name "/HA10_N") (class "Default")
      (node (ref "IC2") (pin "AP26") (pinfunction "IO_L24N_T3_12_AP26") (pintype "bidirectional"))
      (node (ref "R508") (pin "2") (pinfunction "2_2") (pintype "passive"))
    )
    (net (code "50") (name "/HA10_P") (class "Default")
      (node (ref "IC2") (pin "AP25") (pinfunction "IO_L24P_T3_12_AP25") (pintype "bidirectional"))
      (node (ref "R512") (pin "2") (pinfunction "2_2") (pintype "passive"))
    )
    (net (code "51") (name "/HA11_N") (class "Default")
      (node (ref "IC2") (pin "AL33") (pinfunction "IO_L4N_T0_12_AL33") (pintype "bidirectional"))
    )
    (net (code "52") (name "/HA11_P") (class "Default")
      (node (ref "IC2") (pin "AK33") (pinfunction "IO_L4P_T0_12_AK33") (pintype "bidirectional"))
    )
    (net (code "53") (name "/HA12_N") (class "Default")
      (node (ref "IC2") (pin "AN29") (pinfunction "IO_L16N_T2_12_AN29") (pintype "bidirectional"))
      (node (ref "R524") (pin "2") (pinfunction "2_2") (pintype "passive"))
      (node (ref "R525") (pin "1") (pinfunction "1_1") (pintype "passive"))
    )
    (net (code "54") (name "/HA12_P") (class "Default")
      (node (ref "IC2") (pin "AM29") (pinfunction "IO_L16P_T2_12_AM29") (pintype "bidirectional"))
      (node (ref "R528") (pin "2") (pinfunction "2_2") (pintype "passive"))
      (node (ref "R529") (pin "1") (pinfunction "1_1") (pintype "passive"))
    )
    (net (code "55") (name "/HA13_N") (class "Default")
      (node (ref "IC2") (pin "AP28") (pinfunction "IO_L17N_T2_12_AP28") (pintype "bidirectional"))
      (node (ref "R532") (pin "2") (pinfunction "2_2") (pintype "passive"))
      (node (ref "R533") (pin "1") (pinfunction "1_1") (pintype "passive"))
    )
    (net (code "56") (name "/HA13_P") (class "Default")
      (node (ref "IC2") (pin "AN28") (pinfunction "IO_L17P_T2_12_AN28") (pintype "bidirectional"))
      (node (ref "R536") (pin "2") (pinfunction "2_2") (pintype "passive"))
      (node (ref "R537") (pin "1") (pinfunction "1_1") (pintype "passive"))
    )
    (net (code "57") (name "/HA14_N") (class "Default")
      (node (ref "IC2") (pin "AP34") (pinfunction "IO_L3N_T0_DQS_12_AP34") (pintype "bidirectional"))
    )
    (net (code "58") (name "/HA14_P") (class "Default")
      (node (ref "IC2") (pin "AN34") (pinfunction "IO_L3P_T0_DQS_12_AN34") (pintype "bidirectional"))
    )
    (net (code "59") (name "/HA15_N") (class "Default")
      (node (ref "IC2") (pin "AK30") (pinfunction "IO_L11N_T1_SRCC_12_AK30") (pintype "bidirectional"))
    )
    (net (code "60") (name "/HA15_P") (class "Default")
      (node (ref "IC2") (pin "AJ29") (pinfunction "IO_L11P_T1_SRCC_12_AJ29") (pintype "bidirectional"))
    )
    (net (code "61") (name "/HA16_N") (class "Default")
      (node (ref "IC2") (pin "AL27") (pinfunction "IO_L18N_T2_12_AL27") (pintype "bidirectional"))
    )
    (net (code "62") (name "/HA16_P") (class "Default")
      (node (ref "IC2") (pin "AK27") (pinfunction "IO_L18P_T2_12_AK27") (pintype "bidirectional"))
    )
    (net (code "63") (name "/HA17_CC_N") (class "Default")
      (node (ref "IC2") (pin "AK28") (pinfunction "IO_L14N_T2_SRCC_12_AK28") (pintype "bidirectional"))
    )
    (net (code "64") (name "/HA17_CC_P") (class "Default")
      (node (ref "IC2") (pin "AJ28") (pinfunction "IO_L14P_T2_SRCC_12_AJ28") (pintype "bidirectional"))
    )
    (net (code "65") (name "/HA18_N") (class "Default")
      (node (ref "IC2") (pin "AP33") (pinfunction "IO_L5N_T0_12_AP33") (pintype "bidirectional"))
      (node (ref "R215") (pin "2") (pinfunction "2_2") (pintype "passive"))
    )
    (net (code "66") (name "/HA18_P") (class "Default")
      (node (ref "IC2") (pin "AN33") (pinfunction "IO_L5P_T0_12_AN33") (pintype "bidirectional"))
      (node (ref "R249") (pin "2") (pinfunction "2_2") (pintype "passive"))
    )
    (net (code "67") (name "/HA19_N") (class "Default")
      (node (ref "IC2") (pin "AK31") (pinfunction "IO_L9N_T1_DQS_12_AK31") (pintype "bidirectional"))
    )
    (net (code "68") (name "/HA19_P") (class "Default")
      (node (ref "IC2") (pin "AJ30") (pinfunction "IO_L9P_T1_DQS_12_AJ30") (pintype "bidirectional"))
    )
    (net (code "69") (name "/HA20_N") (class "Default")
      (node (ref "IC2") (pin "AK32") (pinfunction "IO_L7N_T1_12_AK32") (pintype "bidirectional"))
    )
    (net (code "70") (name "/HA20_P") (class "Default")
      (node (ref "IC2") (pin "AJ31") (pinfunction "IO_L7P_T1_12_AJ31") (pintype "bidirectional"))
    )
    (net (code "71") (name "/HA21_N") (class "Default")
      (node (ref "IC2") (pin "AP30") (pinfunction "IO_L15N_T2_DQS_12_AP30") (pintype "bidirectional"))
      (node (ref "R516") (pin "2") (pinfunction "2_2") (pintype "passive"))
    )
    (net (code "72") (name "/HA21_P") (class "Default")
      (node (ref "IC2") (pin "AP29") (pinfunction "IO_L15P_T2_DQS_12_AP29") (pintype "bidirectional"))
      (node (ref "R520") (pin "2") (pinfunction "2_2") (pintype "passive"))
    )
    (net (code "73") (name "/HA22_N") (class "Default")
      (node (ref "IC2") (pin "AM34") (pinfunction "IO_L1N_T0_12_AM34") (pintype "bidirectional"))
    )
    (net (code "74") (name "/HA22_P") (class "Default")
      (node (ref "IC2") (pin "AL34") (pinfunction "IO_L1P_T0_12_AL34") (pintype "bidirectional"))
    )
    (net (code "75") (name "/HA23_N") (class "Default")
      (node (ref "IC2") (pin "AJ34") (pinfunction "IO_L2N_T0_12_AJ34") (pintype "bidirectional"))
    )
    (net (code "76") (name "/HA23_P") (class "Default")
      (node (ref "IC2") (pin "AJ33") (pinfunction "IO_L2P_T0_12_AJ33") (pintype "bidirectional"))
    )
    (net (code "77") (name "/HB00_CC_N") (class "Default")
      (node (ref "IC2") (pin "T29") (pinfunction "IO_L11N_T1_SRCC_15_T29") (pintype "bidirectional"))
      (node (ref "R216") (pin "2") (pinfunction "2_2") (pintype "passive"))
      (node (ref "R243") (pin "1") (pinfunction "1_1") (pintype "passive"))
    )
    (net (code "78") (name "/HB00_CC_P") (class "Default")
      (node (ref "IC2") (pin "U29") (pinfunction "IO_L11P_T1_SRCC_15_U29") (pintype "bidirectional"))
      (node (ref "R250") (pin "2") (pinfunction "2_2") (pintype "passive"))
      (node (ref "R251") (pin "1") (pinfunction "1_1") (pintype "passive"))
    )
    (net (code "79") (name "/HB01_N") (class "Default")
      (node (ref "IC2") (pin "M27") (pinfunction "IO_L2N_T0_AD8N_15_M27") (pintype "bidirectional"))
      (node (ref "R358") (pin "2") (pinfunction "2_2") (pintype "passive"))
      (node (ref "R359") (pin "1") (pinfunction "1_1") (pintype "passive"))
    )
    (net (code "80") (name "/HB01_P") (class "Default")
      (node (ref "IC2") (pin "N26") (pinfunction "IO_L2P_T0_AD8P_15_N26") (pintype "bidirectional"))
      (node (ref "R362") (pin "2") (pinfunction "2_2") (pintype "passive"))
      (node (ref "R363") (pin "1") (pinfunction "1_1") (pintype "passive"))
    )
    (net (code "81") (name "/HB2_HB00_CC_N") (class "Default")
      (node (ref "R243") (pin "2") (pinfunction "2_2") (pintype "passive"))
    )
    (net (code "82") (name "/HB2_HB00_CC_P") (class "Default")
      (node (ref "R251") (pin "2") (pinfunction "2_2") (pintype "passive"))
    )
    (net (code "83") (name "/HB2_HB01_N") (class "Default")
      (node (ref "R359") (pin "2") (pinfunction "2_2") (pintype "passive"))
    )
    (net (code "84") (name "/HB2_HB01_P") (class "Default")
      (node (ref "R363") (pin "2") (pinfunction "2_2") (pintype "passive"))
    )
    (net (code "85") (name "/HB2_HB03_N") (class "Default")
      (node (ref "R375") (pin "2") (pinfunction "2_2") (pintype "passive"))
    )
    (net (code "86") (name "/HB2_HB03_P") (class "Default")
      (node (ref "R385") (pin "2") (pinfunction "2_2") (pintype "passive"))
    )
    (net (code "87") (name "/HB2_HB05_N") (class "Default")
      (node (ref "R445") (pin "2") (pinfunction "2_2") (pintype "passive"))
    )
    (net (code "88") (name "/HB2_HB05_P") (class "Default")
      (node (ref "R475") (pin "2") (pinfunction "2_2") (pintype "passive"))
    )
    (net (code "89") (name "/HB2_HB06_CC_N") (class "Default")
      (node (ref "R479") (pin "2") (pinfunction "2_2") (pintype "passive"))
    )
    (net (code "90") (name "/HB2_HB06_CC_P") (class "Default")
      (node (ref "R483") (pin "2") (pinfunction "2_2") (pintype "passive"))
    )
    (net (code "91") (name "/HB2_HB14_N") (class "Default")
      (node (ref "R541") (pin "2") (pinfunction "2_2") (pintype "passive"))
    )
    (net (code "92") (name "/HB2_HB14_P") (class "Default")
      (node (ref "R543") (pin "2") (pinfunction "2_2") (pintype "passive"))
    )
    (net (code "93") (name "/HB2_HB15_N") (class "Default")
      (node (ref "R545") (pin "2") (pinfunction "2_2") (pintype "passive"))
    )
    (net (code "94") (name "/HB2_HB15_P") (class "Default")
      (node (ref "R547") (pin "2") (pinfunction "2_2") (pintype "passive"))
    )
    (net (code "95") (name "/HB2_HB18_N") (class "Default")
      (node (ref "R527") (pin "2") (pinfunction "2_2") (pintype "passive"))
    )
    (net (code "96") (name "/HB2_HB18_P") (class "Default")
      (node (ref "R531") (pin "2") (pinfunction "2_2") (pintype "passive"))
    )
    (net (code "97") (name "/HB02_N") (class "Default")
      (node (ref "IC2") (pin "M34") (pinfunction "IO_L22N_T3_A16_15_M34") (pintype "bidirectional"))
      (node (ref "R366") (pin "2") (pinfunction "2_2") (pintype "passive"))
    )
    (net (code "98") (name "/HB02_P") (class "Default")
      (node (ref "IC2") (pin "N34") (pinfunction "IO_L22P_T3_A17_15_N34") (pintype "bidirectional"))
      (node (ref "R370") (pin "2") (pinfunction "2_2") (pintype "passive"))
    )
    (net (code "99") (name "/HB03_N") (class "Default")
      (node (ref "IC2") (pin "T34") (pinfunction "IO_L23N_T3_FWE_B_15_T34") (pintype "bidirectional"))
      (node (ref "R374") (pin "2") (pinfunction "2_2") (pintype "passive"))
      (node (ref "R375") (pin "1") (pinfunction "1_1") (pintype "passive"))
    )
    (net (code "100") (name "/HB03_P") (class "Default")
      (node (ref "IC2") (pin "U34") (pinfunction "IO_L23P_T3_FOE_B_15_U34") (pintype "bidirectional"))
      (node (ref "R378") (pin "2") (pinfunction "2_2") (pintype "passive"))
      (node (ref "R385") (pin "1") (pinfunction "1_1") (pintype "passive"))
    )
    (net (code "101") (name "/HB04_N") (class "Default")
      (node (ref "IC2") (pin "U27") (pinfunction "IO_L5N_T0_AD9N_15_U27") (pintype "bidirectional"))
    )
    (net (code "102") (name "/HB04_P") (class "Default")
      (node (ref "IC2") (pin "U26") (pinfunction "IO_L5P_T0_AD9P_15_U26") (pintype "bidirectional"))
    )
    (net (code "103") (name "/HB05_N") (class "Default")
      (node (ref "IC2") (pin "P34") (pinfunction "IO_L24N_T3_RS0_15_P34") (pintype "bidirectional"))
      (node (ref "R442") (pin "2") (pinfunction "2_2") (pintype "passive"))
      (node (ref "R445") (pin "1") (pinfunction "1_1") (pintype "passive"))
    )
    (net (code "104") (name "/HB05_P") (class "Default")
      (node (ref "IC2") (pin "P33") (pinfunction "IO_L24P_T3_RS1_15_P33") (pintype "bidirectional"))
      (node (ref "R450") (pin "2") (pinfunction "2_2") (pintype "passive"))
      (node (ref "R475") (pin "1") (pinfunction "1_1") (pintype "passive"))
    )
    (net (code "105") (name "/HB06_CC_N") (class "Default")
      (node (ref "IC2") (pin "P30") (pinfunction "IO_L13N_T2_MRCC_15_P30") (pintype "bidirectional"))
      (node (ref "R478") (pin "2") (pinfunction "2_2") (pintype "passive"))
      (node (ref "R479") (pin "1") (pinfunction "1_1") (pintype "passive"))
    )
    (net (code "106") (name "/HB06_CC_P") (class "Default")
      (node (ref "IC2") (pin "R30") (pinfunction "IO_L13P_T2_MRCC_15_R30") (pintype "bidirectional"))
      (node (ref "R482") (pin "2") (pinfunction "2_2") (pintype "passive"))
      (node (ref "R483") (pin "1") (pinfunction "1_1") (pintype "passive"))
    )
    (net (code "107") (name "/HB07_N") (class "Default")
      (node (ref "IC2") (pin "N24") (pinfunction "IO_L4N_T0_15_N24") (pintype "bidirectional"))
      (node (ref "R486") (pin "2") (pinfunction "2_2") (pintype "passive"))
    )
    (net (code "108") (name "/HB07_P") (class "Default")
      (node (ref "IC2") (pin "P24") (pinfunction "IO_L4P_T0_15_P24") (pintype "bidirectional"))
      (node (ref "R490") (pin "2") (pinfunction "2_2") (pintype "passive"))
    )
    (net (code "109") (name "/HB08_N") (class "Default")
      (node (ref "IC2") (pin "P26") (pinfunction "IO_L1N_T0_AD0N_15_P26") (pintype "bidirectional"))
      (node (ref "R494") (pin "2") (pinfunction "2_2") (pintype "passive"))
    )
    (net (code "110") (name "/HB08_P") (class "Default")
      (node (ref "IC2") (pin "R26") (pinfunction "IO_L1P_T0_AD0P_15_R26") (pintype "bidirectional"))
      (node (ref "R498") (pin "2") (pinfunction "2_2") (pintype "passive"))
    )
    (net (code "111") (name "/HB09_N") (class "Default")
      (node (ref "IC2") (pin "R28") (pinfunction "IO_L9N_T1_DQS_AD3N_15_R28") (pintype "bidirectional"))
      (node (ref "R502") (pin "2") (pinfunction "2_2") (pintype "passive"))
    )
    (net (code "112") (name "/HB09_P") (class "Default")
      (node (ref "IC2") (pin "T28") (pinfunction "IO_L9P_T1_DQS_AD3P_15_T28") (pintype "bidirectional"))
      (node (ref "R506") (pin "2") (pinfunction "2_2") (pintype "passive"))
    )
    (net (code "113") (name "/HB10_N") (class "Default")
      (node (ref "IC2") (pin "T25") (pinfunction "IO_L3N_T0_DQS_AD1N_15_T25") (pintype "bidirectional"))
      (node (ref "R510") (pin "2") (pinfunction "2_2") (pintype "passive"))
    )
    (net (code "114") (name "/HB10_P") (class "Default")
      (node (ref "IC2") (pin "U25") (pinfunction "IO_L3P_T0_DQS_AD1P_15_U25") (pintype "bidirectional"))
      (node (ref "R514") (pin "2") (pinfunction "2_2") (pintype "passive"))
    )
    (net (code "115") (name "/HB11_N") (class "Default")
      (node (ref "IC2") (pin "R27") (pinfunction "IO_L7N_T1_AD2N_15_R27") (pintype "bidirectional"))
      (node (ref "R518") (pin "2") (pinfunction "2_2") (pintype "passive"))
    )
    (net (code "116") (name "/HB11_P") (class "Default")
      (node (ref "IC2") (pin "T27") (pinfunction "IO_L7P_T1_AD2P_15_T27") (pintype "bidirectional"))
      (node (ref "R522") (pin "2") (pinfunction "2_2") (pintype "passive"))
    )
    (net (code "117") (name "/HB12_N") (class "Default")
      (node (ref "IC2") (pin "M32") (pinfunction "IO_L17N_T2_A25_15_M32") (pintype "bidirectional"))
    )
    (net (code "118") (name "/HB12_P") (class "Default")
      (node (ref "IC2") (pin "N31") (pinfunction "IO_L17P_T2_A26_15_N31") (pintype "bidirectional"))
    )
    (net (code "119") (name "/HB13_N") (class "Default")
      (node (ref "IC2") (pin "N28") (pinfunction "IO_L8N_T1_AD10N_15_N28") (pintype "bidirectional"))
      (node (ref "R535") (pin "2") (pinfunction "2_2") (pintype "passive"))
    )
    (net (code "120") (name "/HB13_P") (class "Default")
      (node (ref "IC2") (pin "N27") (pinfunction "IO_L8P_T1_AD10P_15_N27") (pintype "bidirectional"))
      (node (ref "R539") (pin "2") (pinfunction "2_2") (pintype "passive"))
    )
    (net (code "121") (name "/HB14_N") (class "Default")
      (node (ref "IC2") (pin "P31") (pinfunction "IO_L16N_T2_A27_15_P31") (pintype "bidirectional"))
      (node (ref "R540") (pin "2") (pinfunction "2_2") (pintype "passive"))
      (node (ref "R541") (pin "1") (pinfunction "1_1") (pintype "passive"))
    )
    (net (code "122") (name "/HB14_P") (class "Default")
      (node (ref "IC2") (pin "R31") (pinfunction "IO_L16P_T2_A28_15_R31") (pintype "bidirectional"))
      (node (ref "R542") (pin "2") (pinfunction "2_2") (pintype "passive"))
      (node (ref "R543") (pin "1") (pinfunction "1_1") (pintype "passive"))
    )
    (net (code "123") (name "/HB15_N") (class "Default")
      (node (ref "IC2") (pin "T30") (pinfunction "IO_L14N_T2_SRCC_15_T30") (pintype "bidirectional"))
      (node (ref "R544") (pin "2") (pinfunction "2_2") (pintype "passive"))
      (node (ref "R545") (pin "1") (pinfunction "1_1") (pintype "passive"))
    )
    (net (code "124") (name "/HB15_P") (class "Default")
      (node (ref "IC2") (pin "U30") (pinfunction "IO_L14P_T2_SRCC_15_U30") (pintype "bidirectional"))
      (node (ref "R546") (pin "2") (pinfunction "2_2") (pintype "passive"))
      (node (ref "R547") (pin "1") (pinfunction "1_1") (pintype "passive"))
    )
    (net (code "125") (name "/HB16_N") (class "Default")
      (node (ref "IC2") (pin "U32") (pinfunction "IO_L18N_T2_A23_15_U32") (pintype "bidirectional"))
    )
    (net (code "126") (name "/HB16_P") (class "Default")
      (node (ref "IC2") (pin "U31") (pinfunction "IO_L18P_T2_A24_15_U31") (pintype "bidirectional"))
    )
    (net (code "127") (name "/HB17_CC_N") (class "Default")
      (node (ref "IC2") (pin "P29") (pinfunction "IO_L12N_T1_MRCC_15_P29") (pintype "bidirectional"))
      (node (ref "R548") (pin "2") (pinfunction "2_2") (pintype "passive"))
    )
    (net (code "128") (name "/HB17_CC_P") (class "Default")
      (node (ref "IC2") (pin "P28") (pinfunction "IO_L12P_T1_MRCC_15_P28") (pintype "bidirectional"))
      (node (ref "R549") (pin "2") (pinfunction "2_2") (pintype "passive"))
    )
    (net (code "129") (name "/HB18_N") (class "Default")
      (node (ref "IC2") (pin "M29") (pinfunction "IO_L10N_T1_AD11N_15_M29") (pintype "bidirectional"))
      (node (ref "R526") (pin "2") (pinfunction "2_2") (pintype "passive"))
      (node (ref "R527") (pin "1") (pinfunction "1_1") (pintype "passive"))
    )
    (net (code "130") (name "/HB18_P") (class "Default")
      (node (ref "IC2") (pin "N29") (pinfunction "IO_L10P_T1_AD11P_15_N29") (pintype "bidirectional"))
      (node (ref "R530") (pin "2") (pinfunction "2_2") (pintype "passive"))
      (node (ref "R531") (pin "1") (pinfunction "1_1") (pintype "passive"))
    )
    (net (code "131") (name "/HB19_N") (class "Default")
      (node (ref "IC2") (pin "M31") (pinfunction "IO_L15N_T2_DQS_ADV_B_15_M31") (pintype "bidirectional"))
    )
    (net (code "132") (name "/HB19_P") (class "Default")
      (node (ref "IC2") (pin "M30") (pinfunction "IO_L15P_T2_DQS_15_M30") (pintype "bidirectional"))
    )
    (net (code "133") (name "/HB20_N") (class "Default")
      (node (ref "IC2") (pin "N33") (pinfunction "IO_L20N_T3_A19_15_N33") (pintype "bidirectional"))
    )
    (net (code "134") (name "/HB20_P") (class "Default")
      (node (ref "IC2") (pin "N32") (pinfunction "IO_L20P_T3_A20_15_N32") (pintype "bidirectional"))
    )
    (net (code "135") (name "/HB21_N") (class "Default")
      (node (ref "IC2") (pin "R33") (pinfunction "IO_L21N_T3_DQS_A18_15_R33") (pintype "bidirectional"))
      (node (ref "R534") (pin "2") (pinfunction "2_2") (pintype "passive"))
    )
    (net (code "136") (name "/HB21_P") (class "Default")
      (node (ref "IC2") (pin "T33") (pinfunction "IO_L21P_T3_DQS_15_T33") (pintype "bidirectional"))
      (node (ref "R538") (pin "2") (pinfunction "2_2") (pintype "passive"))
    )
    (net (code "137") (name "/I2C_RST") (class "Default")
      (node (ref "IC2") (pin "AD31") (pinfunction "IO_L7P_T1_13_AD31") (pintype "bidirectional"))
    )
    (net (code "138") (name "/LA2_LA00_CC_N") (class "Default")
      (node (ref "IC2") (pin "AF28") (pinfunction "IO_L14N_T2_SRCC_13_AF28") (pintype "bidirectional"))
    )
    (net (code "139") (name "/LA2_LA00_CC_P") (class "Default")
      (node (ref "IC2") (pin "AE28") (pinfunction "IO_L14P_T2_SRCC_13_AE28") (pintype "bidirectional"))
    )
    (net (code "140") (name "/LA2_LA01_CC_N") (class "Default")
      (node (ref "IC2") (pin "AF30") (pinfunction "IO_L11N_T1_SRCC_13_AF30") (pintype "bidirectional"))
    )
    (net (code "141") (name "/LA2_LA01_CC_P") (class "Default")
      (node (ref "IC2") (pin "AF29") (pinfunction "IO_L11P_T1_SRCC_13_AF29") (pintype "bidirectional"))
    )
    (net (code "142") (name "/LA2_LA02_N") (class "Default")
      (node (ref "IC2") (pin "AH31") (pinfunction "IO_L10N_T1_13_AH31") (pintype "bidirectional"))
    )
    (net (code "143") (name "/LA2_LA02_P") (class "Default")
      (node (ref "IC2") (pin "AG31") (pinfunction "IO_L10P_T1_13_AG31") (pintype "bidirectional"))
    )
    (net (code "144") (name "/LA2_LA03_N") (class "Default")
      (node (ref "IC2") (pin "AH24") (pinfunction "IO_L21N_T3_DQS_13_AH24") (pintype "bidirectional"))
    )
    (net (code "145") (name "/LA2_LA03_P") (class "Default")
      (node (ref "IC2") (pin "AG24") (pinfunction "IO_L21P_T3_DQS_13_AG24") (pintype "bidirectional"))
    )
    (net (code "146") (name "/LA2_LA04_N") (class "Default")
      (node (ref "IC2") (pin "AC27") (pinfunction "IO_L16N_T2_13_AC27") (pintype "bidirectional"))
    )
    (net (code "147") (name "/LA2_LA04_P") (class "Default")
      (node (ref "IC2") (pin "AC26") (pinfunction "IO_L16P_T2_13_AC26") (pintype "bidirectional"))
    )
    (net (code "148") (name "/LA2_LA05_N") (class "Default")
      (node (ref "IC2") (pin "AH34") (pinfunction "IO_L3N_T0_DQS_13_AH34") (pintype "bidirectional"))
    )
    (net (code "149") (name "/LA2_LA05_P") (class "Default")
      (node (ref "IC2") (pin "AH33") (pinfunction "IO_L3P_T0_DQS_13_AH33") (pintype "bidirectional"))
    )
    (net (code "150") (name "/LA2_LA06_N") (class "Default")
      (node (ref "IC2") (pin "AF23") (pinfunction "IO_L20N_T3_13_AF23") (pintype "bidirectional"))
    )
    (net (code "151") (name "/LA2_LA06_P") (class "Default")
      (node (ref "IC2") (pin "AE23") (pinfunction "IO_L20P_T3_13_AE23") (pintype "bidirectional"))
    )
    (net (code "152") (name "/LA2_LA07_N") (class "Default")
      (node (ref "IC2") (pin "AH27") (pinfunction "IO_L17N_T2_13_AH27") (pintype "bidirectional"))
    )
    (net (code "153") (name "/LA2_LA07_P") (class "Default")
      (node (ref "IC2") (pin "AG27") (pinfunction "IO_L17P_T2_13_AG27") (pintype "bidirectional"))
    )
    (net (code "154") (name "/LA2_LA08_N") (class "Default")
      (node (ref "IC2") (pin "AE25") (pinfunction "IO_L24N_T3_13_AE25") (pintype "bidirectional"))
    )
    (net (code "155") (name "/LA2_LA08_P") (class "Default")
      (node (ref "IC2") (pin "AD25") (pinfunction "IO_L24P_T3_13_AD25") (pintype "bidirectional"))
    )
    (net (code "156") (name "/LA2_LA09_N") (class "Default")
      (node (ref "IC2") (pin "AG25") (pinfunction "IO_L23N_T3_13_AG25") (pintype "bidirectional"))
    )
    (net (code "157") (name "/LA2_LA09_P") (class "Default")
      (node (ref "IC2") (pin "AF25") (pinfunction "IO_L23P_T3_13_AF25") (pintype "bidirectional"))
    )
    (net (code "158") (name "/LA2_LA10_N") (class "Default")
      (node (ref "IC2") (pin "AH32") (pinfunction "IO_L5N_T0_13_AH32") (pintype "bidirectional"))
    )
    (net (code "159") (name "/LA2_LA10_P") (class "Default")
      (node (ref "IC2") (pin "AG32") (pinfunction "IO_L5P_T0_13_AG32") (pintype "bidirectional"))
    )
    (net (code "160") (name "/LA2_LA11_N") (class "Default")
      (node (ref "IC2") (pin "AE30") (pinfunction "IO_L8N_T1_13_AE30") (pintype "bidirectional"))
    )
    (net (code "161") (name "/LA2_LA11_P") (class "Default")
      (node (ref "IC2") (pin "AD30") (pinfunction "IO_L8P_T1_13_AD30") (pintype "bidirectional"))
    )
    (net (code "162") (name "/LA2_LA12_N") (class "Default")
      (node (ref "IC2") (pin "AF27") (pinfunction "IO_L18N_T2_13_AF27") (pintype "bidirectional"))
    )
    (net (code "163") (name "/LA2_LA12_P") (class "Default")
      (node (ref "IC2") (pin "AE27") (pinfunction "IO_L18P_T2_13_AE27") (pintype "bidirectional"))
    )
    (net (code "164") (name "/LA2_LA13_N") (class "Default")
      (node (ref "IC2") (pin "AG34") (pinfunction "IO_L1N_T0_13_AG34") (pintype "bidirectional"))
    )
    (net (code "165") (name "/LA2_LA13_P") (class "Default")
      (node (ref "IC2") (pin "AF34") (pinfunction "IO_L1P_T0_13_AF34") (pintype "bidirectional"))
    )
    (net (code "166") (name "/LA2_LA14_N") (class "Default")
      (node (ref "IC2") (pin "AF33") (pinfunction "IO_L4N_T0_13_AF33") (pintype "bidirectional"))
    )
    (net (code "167") (name "/LA2_LA14_P") (class "Default")
      (node (ref "IC2") (pin "AE33") (pinfunction "IO_L4P_T0_13_AE33") (pintype "bidirectional"))
    )
    (net (code "168") (name "/LA2_LA15_N") (class "Default")
      (node (ref "IC2") (pin "AD29") (pinfunction "IO_L9N_T1_DQS_13_AD29") (pintype "bidirectional"))
    )
    (net (code "169") (name "/LA2_LA15_P") (class "Default")
      (node (ref "IC2") (pin "AD28") (pinfunction "IO_L9P_T1_DQS_13_AD28") (pintype "bidirectional"))
    )
    (net (code "170") (name "/LA2_LA16_N") (class "Default")
      (node (ref "IC2") (pin "AD34") (pinfunction "IO_L2N_T0_13_AD34") (pintype "bidirectional"))
    )
    (net (code "171") (name "/LA2_LA16_P") (class "Default")
      (node (ref "IC2") (pin "AD33") (pinfunction "IO_L2P_T0_13_AD33") (pintype "bidirectional"))
    )
    (net (code "172") (name "/LA2_LA17_CC_N") (class "Default")
      (node (ref "IC2") (pin "AB32") (pinfunction "IO_L14N_T2_SRCC_14_AB32") (pintype "bidirectional"))
    )
    (net (code "173") (name "/LA2_LA17_CC_P") (class "Default")
      (node (ref "IC2") (pin "AB31") (pinfunction "IO_L14P_T2_SRCC_14_AB31") (pintype "bidirectional"))
    )
    (net (code "174") (name "/LA2_LA18_CC_N") (class "Default")
      (node (ref "IC2") (pin "W31") (pinfunction "IO_L11N_T1_SRCC_14_W31") (pintype "bidirectional"))
    )
    (net (code "175") (name "/LA2_LA18_CC_P") (class "Default")
      (node (ref "IC2") (pin "W30") (pinfunction "IO_L11P_T1_SRCC_14_W30") (pintype "bidirectional"))
    )
    (net (code "176") (name "/LA2_LA19_N") (class "Default")
      (node (ref "IC2") (pin "AB27") (pinfunction "IO_L21N_T3_DQS_A06_D22_14_AB27") (pintype "bidirectional"))
    )
    (net (code "177") (name "/LA2_LA19_P") (class "Default")
      (node (ref "IC2") (pin "AB26") (pinfunction "IO_L21P_T3_DQS_14_AB26") (pintype "bidirectional"))
    )
    (net (code "178") (name "/LA2_LA20_N") (class "Default")
      (node (ref "IC2") (pin "AB25") (pinfunction "IO_L24N_T3_A00_D16_14_AB25") (pintype "bidirectional"))
    )
    (net (code "179") (name "/LA2_LA20_P") (class "Default")
      (node (ref "IC2") (pin "AB24") (pinfunction "IO_L24P_T3_A01_D17_14_AB24") (pintype "bidirectional"))
    )
    (net (code "180") (name "/LA2_LA21_N") (class "Default")
      (node (ref "IC2") (pin "AA33") (pinfunction "IO_L16N_T2_A15_D31_14_AA33") (pintype "bidirectional"))
    )
    (net (code "181") (name "/LA2_LA21_P") (class "Default")
      (node (ref "IC2") (pin "AA32") (pinfunction "IO_L16P_T2_CSI_B_14_AA32") (pintype "bidirectional"))
    )
    (net (code "182") (name "/LA2_LA22_N") (class "Default")
      (node (ref "IC2") (pin "AA25") (pinfunction "IO_L23N_T3_A02_D18_14_AA25") (pintype "bidirectional"))
    )
    (net (code "183") (name "/LA2_LA22_P") (class "Default")
      (node (ref "IC2") (pin "AA24") (pinfunction "IO_L23P_T3_A03_D19_14_AA24") (pintype "bidirectional"))
    )
    (net (code "184") (name "/LA2_LA23_N") (class "Default")
      (node (ref "IC2") (pin "Y25") (pinfunction "IO_L5N_T0_D07_14_Y25") (pintype "bidirectional"))
    )
    (net (code "185") (name "/LA2_LA23_P") (class "Default")
      (node (ref "IC2") (pin "W25") (pinfunction "IO_L5P_T0_D06_14_W25") (pintype "bidirectional"))
    )
    (net (code "186") (name "/LA2_LA24_N") (class "Default")
      (node (ref "IC2") (pin "Y33") (pinfunction "IO_L10N_T1_D15_14_Y33") (pintype "bidirectional"))
    )
    (net (code "187") (name "/LA2_LA24_P") (class "Default")
      (node (ref "IC2") (pin "Y32") (pinfunction "IO_L10P_T1_D14_14_Y32") (pintype "bidirectional"))
    )
    (net (code "188") (name "/LA2_LA25_N") (class "Default")
      (node (ref "IC2") (pin "AB29") (pinfunction "IO_L22N_T3_A04_D20_14_AB29") (pintype "bidirectional"))
    )
    (net (code "189") (name "/LA2_LA25_P") (class "Default")
      (node (ref "IC2") (pin "AA29") (pinfunction "IO_L22P_T3_A05_D21_14_AA29") (pintype "bidirectional"))
    )
    (net (code "190") (name "/LA2_LA26_N") (class "Default")
      (node (ref "IC2") (pin "AC32") (pinfunction "IO_L17N_T2_A13_D29_14_AC32") (pintype "bidirectional"))
    )
    (net (code "191") (name "/LA2_LA26_P") (class "Default")
      (node (ref "IC2") (pin "AC31") (pinfunction "IO_L17P_T2_A14_D30_14_AC31") (pintype "bidirectional"))
    )
    (net (code "192") (name "/LA2_LA27_N") (class "Default")
      (node (ref "IC2") (pin "AA28") (pinfunction "IO_L20N_T3_A07_D23_14_AA28") (pintype "bidirectional"))
    )
    (net (code "193") (name "/LA2_LA27_P") (class "Default")
      (node (ref "IC2") (pin "AA27") (pinfunction "IO_L20P_T3_A08_D24_14_AA27") (pintype "bidirectional"))
    )
    (net (code "194") (name "/LA2_LA28_N") (class "Default")
      (node (ref "IC2") (pin "W29") (pinfunction "IO_L4N_T0_D05_14_W29") (pintype "bidirectional"))
    )
    (net (code "195") (name "/LA2_LA28_P") (class "Default")
      (node (ref "IC2") (pin "W28") (pinfunction "IO_L4P_T0_D04_14_W28") (pintype "bidirectional"))
    )
    (net (code "196") (name "/LA2_LA29_N") (class "Default")
      (node (ref "IC2") (pin "AC34") (pinfunction "IO_L15N_T2_DQS_DOUT_CSO_B_14_AC34") (pintype "bidirectional"))
    )
    (net (code "197") (name "/LA2_LA29_P") (class "Default")
      (node (ref "IC2") (pin "AC33") (pinfunction "IO_L15P_T2_DQS_RDWR_B_14_AC33") (pintype "bidirectional"))
    )
    (net (code "198") (name "/LA2_LA30_N") (class "Default")
      (node (ref "IC2") (pin "W34") (pinfunction "IO_L8N_T1_D12_14_W34") (pintype "bidirectional"))
    )
    (net (code "199") (name "/LA2_LA30_P") (class "Default")
      (node (ref "IC2") (pin "W33") (pinfunction "IO_L8P_T1_D11_14_W33") (pintype "bidirectional"))
    )
    (net (code "200") (name "/LA2_LA31_N") (class "Default")
      (node (ref "IC2") (pin "V32") (pinfunction "IO_L7N_T1_D10_14_V32") (pintype "bidirectional"))
    )
    (net (code "201") (name "/LA2_LA31_P") (class "Default")
      (node (ref "IC2") (pin "V31") (pinfunction "IO_L7P_T1_D09_14_V31") (pintype "bidirectional"))
    )
    (net (code "202") (name "/LA2_LA32_N") (class "Default")
      (node (ref "IC2") (pin "AB34") (pinfunction "IO_L18N_T2_A11_D27_14_AB34") (pintype "bidirectional"))
    )
    (net (code "203") (name "/LA2_LA32_P") (class "Default")
      (node (ref "IC2") (pin "AA34") (pinfunction "IO_L18P_T2_A12_D28_14_AA34") (pintype "bidirectional"))
    )
    (net (code "204") (name "/LA2_LA33_N") (class "Default")
      (node (ref "IC2") (pin "V34") (pinfunction "IO_L9N_T1_DQS_D13_14_V34") (pintype "bidirectional"))
    )
    (net (code "205") (name "/LA2_LA33_P") (class "Default")
      (node (ref "IC2") (pin "V33") (pinfunction "IO_L9P_T1_DQS_14_V33") (pintype "bidirectional"))
    )
    (net (code "206") (name "/PRI_UART_Rx") (class "Default")
      (node (ref "IC2") (pin "AD26") (pinfunction "IO_L15P_T2_DQS_13_AD26") (pintype "bidirectional"))
      (node (ref "TP15") (pin "1") (pintype "passive"))
    )
    (net (code "207") (name "/PRI_UART_Tx") (class "Default")
      (node (ref "IC2") (pin "AE26") (pinfunction "IO_L15N_T2_DQS_13_AE26") (pintype "bidirectional"))
      (node (ref "TP14") (pin "1") (pintype "passive"))
    )
    (net (code "208") (name "/PUDC") (class "Default")
      (node (ref "IC2") (pin "W26") (pinfunction "IO_L3P_T0_DQS_PUDC_B_14_W26") (pintype "bidirectional"))
      (node (ref "R180") (pin "1") (pinfunction "1_1") (pintype "passive"))
    )
    (net (code "209") (name "/RTM.P30_IO5_AB_B1_CC_N") (class "Default")
      (node (ref "R252") (pin "1") (pinfunction "1_1") (pintype "passive"))
    )
    (net (code "210") (name "/RTM.P30_IO5_AB_B1_CC_P") (class "Default")
      (node (ref "R360") (pin "1") (pinfunction "1_1") (pintype "passive"))
    )
    (net (code "211") (name "/RTM.P30_IO5_CD_B1_N") (class "Default")
      (node (ref "R492") (pin "1") (pinfunction "1_1") (pintype "passive"))
    )
    (net (code "212") (name "/RTM.P30_IO5_CD_B1_P") (class "Default")
      (node (ref "R496") (pin "1") (pinfunction "1_1") (pintype "passive"))
    )
    (net (code "213") (name "/RTM.P30_IO5_EF_B1_N") (class "Default")
      (node (ref "R438") (pin "1") (pinfunction "1_1") (pintype "passive"))
    )
    (net (code "214") (name "/RTM.P30_IO5_EF_B1_P") (class "Default")
      (node (ref "R448") (pin "1") (pinfunction "1_1") (pintype "passive"))
    )
    (net (code "215") (name "/RTM.P30_IO6_AB_B1_CC_N") (class "Default")
      (node (ref "R51") (pin "1") (pinfunction "1_1") (pintype "passive"))
    )
    (net (code "216") (name "/RTM.P30_IO6_AB_B1_CC_P") (class "Default")
      (node (ref "R245") (pin "1") (pinfunction "1_1") (pintype "passive"))
    )
    (net (code "217") (name "/RTM.P30_IO6_CD_B1_N") (class "Default")
      (node (ref "R532") (pin "1") (pinfunction "1_1") (pintype "passive"))
    )
    (net (code "218") (name "/RTM.P30_IO6_CD_B1_P") (class "Default")
      (node (ref "R536") (pin "1") (pinfunction "1_1") (pintype "passive"))
    )
    (net (code "219") (name "/RTM.P30_IO6_EF_B1_N") (class "Default")
      (node (ref "R386") (pin "1") (pinfunction "1_1") (pintype "passive"))
    )
    (net (code "220") (name "/RTM.P30_IO6_EF_B1_P") (class "Default")
      (node (ref "R390") (pin "1") (pinfunction "1_1") (pintype "passive"))
    )
    (net (code "221") (name "/RTM.P30_IO7_AB_B1_N") (class "Default")
      (node (ref "R524") (pin "1") (pinfunction "1_1") (pintype "passive"))
    )
    (net (code "222") (name "/RTM.P30_IO7_AB_B1_P") (class "Default")
      (node (ref "R528") (pin "1") (pinfunction "1_1") (pintype "passive"))
    )
    (net (code "223") (name "/RTM.P30_IO7_CD_B1_N") (class "Default")
      (node (ref "R500") (pin "1") (pinfunction "1_1") (pintype "passive"))
    )
    (net (code "224") (name "/RTM.P30_IO7_CD_B1_P") (class "Default")
      (node (ref "R504") (pin "1") (pinfunction "1_1") (pintype "passive"))
    )
    (net (code "225") (name "/RTM.P30_IO7_EF_B1_N") (class "Default")
      (node (ref "R476") (pin "1") (pinfunction "1_1") (pintype "passive"))
    )
    (net (code "226") (name "/RTM.P30_IO7_EF_B1_P") (class "Default")
      (node (ref "R480") (pin "1") (pinfunction "1_1") (pintype "passive"))
    )
    (net (code "227") (name "/RTM.P30_IO8_AB_B1_N") (class "Default")
      (node (ref "R508") (pin "1") (pinfunction "1_1") (pintype "passive"))
    )
    (net (code "228") (name "/RTM.P30_IO8_AB_B1_P") (class "Default")
      (node (ref "R512") (pin "1") (pinfunction "1_1") (pintype "passive"))
    )
    (net (code "229") (name "/RTM.P30_IO8_CD_B1_N") (class "Default")
      (node (ref "R516") (pin "1") (pinfunction "1_1") (pintype "passive"))
    )
    (net (code "230") (name "/RTM.P30_IO8_CD_B1_P") (class "Default")
      (node (ref "R520") (pin "1") (pinfunction "1_1") (pintype "passive"))
    )
    (net (code "231") (name "/RTM.P30_IO8_EF_B1_N") (class "Default")
      (node (ref "R215") (pin "1") (pinfunction "1_1") (pintype "passive"))
    )
    (net (code "232") (name "/RTM.P30_IO8_EF_B1_P") (class "Default")
      (node (ref "R249") (pin "1") (pinfunction "1_1") (pintype "passive"))
    )
    (net (code "233") (name "/RTM.P30_IO9_AB_B2_CC_N") (class "Default")
      (node (ref "R478") (pin "1") (pinfunction "1_1") (pintype "passive"))
    )
    (net (code "234") (name "/RTM.P30_IO9_AB_B2_CC_P") (class "Default")
      (node (ref "R482") (pin "1") (pinfunction "1_1") (pintype "passive"))
    )
    (net (code "235") (name "/RTM.P30_IO9_CD_B2_N") (class "Default")
      (node (ref "R366") (pin "1") (pinfunction "1_1") (pintype "passive"))
    )
    (net (code "236") (name "/RTM.P30_IO9_CD_B2_P") (class "Default")
      (node (ref "R370") (pin "1") (pinfunction "1_1") (pintype "passive"))
    )
    (net (code "237") (name "/RTM.P30_IO9_EF_B2_N") (class "Default")
      (node (ref "R486") (pin "1") (pinfunction "1_1") (pintype "passive"))
    )
    (net (code "238") (name "/RTM.P30_IO9_EF_B2_P") (class "Default")
      (node (ref "R490") (pin "1") (pinfunction "1_1") (pintype "passive"))
    )
    (net (code "239") (name "/RTM.P30_IO10_AB_B2_CC_N") (class "Default")
      (node (ref "R216") (pin "1") (pinfunction "1_1") (pintype "passive"))
    )
    (net (code "240") (name "/RTM.P30_IO10_AB_B2_CC_P") (class "Default")
      (node (ref "R250") (pin "1") (pinfunction "1_1") (pintype "passive"))
    )
    (net (code "241") (name "/RTM.P30_IO10_CD_B2_N") (class "Default")
      (node (ref "R502") (pin "1") (pinfunction "1_1") (pintype "passive"))
    )
    (net (code "242") (name "/RTM.P30_IO10_CD_B2_P") (class "Default")
      (node (ref "R506") (pin "1") (pinfunction "1_1") (pintype "passive"))
    )
    (net (code "243") (name "/RTM.P30_IO10_EF_B2_N") (class "Default")
      (node (ref "R494") (pin "1") (pinfunction "1_1") (pintype "passive"))
    )
    (net (code "244") (name "/RTM.P30_IO10_EF_B2_P") (class "Default")
      (node (ref "R498") (pin "1") (pinfunction "1_1") (pintype "passive"))
    )
    (net (code "245") (name "/RTM.P30_OUT0_N") (class "Default")
      (node (ref "R372") (pin "1") (pinfunction "1_1") (pintype "passive"))
    )
    (net (code "246") (name "/RTM.P30_OUT0_P") (class "Default")
      (node (ref "R376") (pin "1") (pinfunction "1_1") (pintype "passive"))
    )
    (net (code "247") (name "/RTM.P30_OUT1_N") (class "Default")
      (node (ref "R484") (pin "1") (pinfunction "1_1") (pintype "passive"))
    )
    (net (code "248") (name "/RTM.P30_OUT1_P") (class "Default")
      (node (ref "R488") (pin "1") (pinfunction "1_1") (pintype "passive"))
    )
    (net (code "249") (name "/RTM.P30_OUT2_N") (class "Default")
      (node (ref "R364") (pin "1") (pinfunction "1_1") (pintype "passive"))
    )
    (net (code "250") (name "/RTM.P30_OUT2_P") (class "Default")
      (node (ref "R368") (pin "1") (pinfunction "1_1") (pintype "passive"))
    )
    (net (code "251") (name "/RTM.P31_IO1_AB_B2_N") (class "Default")
      (node (ref "R510") (pin "1") (pinfunction "1_1") (pintype "passive"))
    )
    (net (code "252") (name "/RTM.P31_IO1_AB_B2_P") (class "Default")
      (node (ref "R514") (pin "1") (pinfunction "1_1") (pintype "passive"))
    )
    (net (code "253") (name "/RTM.P31_IO1_CD_B2_N") (class "Default")
      (node (ref "R518") (pin "1") (pinfunction "1_1") (pintype "passive"))
    )
    (net (code "254") (name "/RTM.P31_IO1_CD_B2_P") (class "Default")
      (node (ref "R522") (pin "1") (pinfunction "1_1") (pintype "passive"))
    )
    (net (code "255") (name "/RTM.P31_IO1_EF_B2_N") (class "Default")
      (node (ref "R535") (pin "1") (pinfunction "1_1") (pintype "passive"))
    )
    (net (code "256") (name "/RTM.P31_IO1_EF_B2_P") (class "Default")
      (node (ref "R539") (pin "1") (pinfunction "1_1") (pintype "passive"))
    )
    (net (code "257") (name "/RTM.P31_IO2_AB_B2_N") (class "Default")
      (node (ref "R358") (pin "1") (pinfunction "1_1") (pintype "passive"))
    )
    (net (code "258") (name "/RTM.P31_IO2_AB_B2_P") (class "Default")
      (node (ref "R362") (pin "1") (pinfunction "1_1") (pintype "passive"))
    )
    (net (code "259") (name "/RTM.P31_IO2_CD_B2_N") (class "Default")
      (node (ref "R374") (pin "1") (pinfunction "1_1") (pintype "passive"))
    )
    (net (code "260") (name "/RTM.P31_IO2_CD_B2_P") (class "Default")
      (node (ref "R378") (pin "1") (pinfunction "1_1") (pintype "passive"))
    )
    (net (code "261") (name "/RTM.P31_IO2_EF_B2_N") (class "Default")
      (node (ref "R442") (pin "1") (pinfunction "1_1") (pintype "passive"))
    )
    (net (code "262") (name "/RTM.P31_IO2_EF_B2_P") (class "Default")
      (node (ref "R450") (pin "1") (pinfunction "1_1") (pintype "passive"))
    )
    (net (code "263") (name "/RTM.P31_IO3_AB_B2_N") (class "Default")
      (node (ref "R534") (pin "1") (pinfunction "1_1") (pintype "passive"))
    )
    (net (code "264") (name "/RTM.P31_IO3_AB_B2_P") (class "Default")
      (node (ref "R538") (pin "1") (pinfunction "1_1") (pintype "passive"))
    )
    (net (code "265") (name "/RTM.P31_IO4_AB_B2_N") (class "Default")
      (node (ref "R526") (pin "1") (pinfunction "1_1") (pintype "passive"))
    )
    (net (code "266") (name "/RTM.P31_IO4_AB_B2_P") (class "Default")
      (node (ref "R530") (pin "1") (pinfunction "1_1") (pintype "passive"))
    )
    (net (code "267") (name "/RTM.P31_IO7_AB_B3_CC_N") (class "Default")
      (node (ref "R548") (pin "1") (pinfunction "1_1") (pintype "passive"))
    )
    (net (code "268") (name "/RTM.P31_IO7_AB_B3_CC_P") (class "Default")
      (node (ref "R549") (pin "1") (pinfunction "1_1") (pintype "passive"))
    )
    (net (code "269") (name "/RTM.P31_IO8_AB_B3_CC_N") (class "Default")
      (node (ref "R544") (pin "1") (pinfunction "1_1") (pintype "passive"))
    )
    (net (code "270") (name "/RTM.P31_IO8_AB_B3_CC_P") (class "Default")
      (node (ref "R546") (pin "1") (pinfunction "1_1") (pintype "passive"))
    )
    (net (code "271") (name "/VADJ2_PLL_DAC1_DIN") (class "Default")
      (node (ref "IC2") (pin "AF24") (pinfunction "IO_25_13_AF24") (pintype "bidirectional"))
    )
    (net (code "272") (name "/VADJ2_PLL_DAC1_SCLK") (class "Default")
      (node (ref "IC2") (pin "AJ24") (pinfunction "IO_0_12_AJ24") (pintype "bidirectional"))
    )
    (net (code "273") (name "/VADJ2_PLL_DAC2_DIN") (class "Default")
      (node (ref "IC2") (pin "AE32") (pinfunction "IO_L6P_T0_13_AE32") (pintype "bidirectional"))
    )
    (net (code "274") (name "/VADJ2_PLL_DAC2_SCLK") (class "Default")
      (node (ref "IC2") (pin "AL24") (pinfunction "IO_25_12_AL24") (pintype "bidirectional"))
    )
    (net (code "275") (name "/VADJ2_SI57X_OE") (class "Default")
      (node (ref "IC2") (pin "AD23") (pinfunction "IO_0_13_AD23") (pintype "bidirectional"))
    )
    (net (code "276") (name "/VADJ2_SI57X_PRI_SCL") (class "Default")
      (node (ref "IC2") (pin "V24") (pinfunction "IO_0_14_V24") (pintype "bidirectional"))
    )
    (net (code "277") (name "/VADJ2_SI57X_PRI_SDA") (class "Default")
      (node (ref "IC2") (pin "W24") (pinfunction "IO_25_14_W24") (pintype "bidirectional"))
    )
    (net (code "278") (name "/VADJ2_SI57X_PRI_TUNE{slash}SYNC") (class "Default")
      (node (ref "IC2") (pin "T24") (pinfunction "IO_0_15_T24") (pintype "bidirectional"))
    )
    (net (code "279") (name "/VADJ2_SI57X_SEC_TUNE{slash}SYNC") (class "Default")
      (node (ref "IC2") (pin "U24") (pinfunction "IO_25_15_U24") (pintype "bidirectional"))
    )
    (net (code "280") (name "/Vbias_bank14") (class "Default")
      (node (ref "C416") (pin "1") (pinfunction "1_1") (pintype "passive"))
      (node (ref "C459") (pin "1") (pinfunction "1_1") (pintype "passive"))
      (node (ref "C468") (pin "1") (pinfunction "1_1") (pintype "passive"))
      (node (ref "R123") (pin "2") (pinfunction "2_2") (pintype "passive"))
      (node (ref "R148") (pin "2") (pinfunction "2_2") (pintype "passive"))
      (node (ref "R149") (pin "2") (pinfunction "2_2") (pintype "passive"))
      (node (ref "R300") (pin "2") (pinfunction "2_2") (pintype "passive"))
      (node (ref "R306") (pin "2") (pinfunction "2_2") (pintype "passive"))
      (node (ref "R319") (pin "2") (pinfunction "2_2") (pintype "passive"))
    )
    (net (code "290") (name "GND") (class "Default")
      (node (ref "C124") (pin "2") (pinfunction "2_2") (pintype "passive"))
      (node (ref "C125") (pin "2") (pinfunction "2_2") (pintype "passive"))
      (node (ref "C129") (pin "2") (pinfunction "2_2") (pintype "passive"))
      (node (ref "C131") (pin "2") (pinfunction "2_2") (pintype "passive"))
      (node (ref "C132") (pin "2") (pinfunction "2_2") (pintype "passive"))
      (node (ref "C392") (pin "2") (pinfunction "2_2") (pintype "passive"))
      (node (ref "C416") (pin "2") (pinfunction "2_2") (pintype "passive"))
      (node (ref "C459") (pin "2") (pinfunction "2_2") (pintype "passive"))
      (node (ref "C468") (pin "2") (pinfunction "2_2") (pintype "passive"))
      (node (ref "R148") (pin "1") (pinfunction "1_1") (pintype "passive"))
      (node (ref "R180") (pin "2") (pinfunction "2_2") (pintype "passive"))
    )
    (net (code "291") (name "Net-(IC2C-IO_L12N_T1_MRCC_14)") (class "Default")
      (node (ref "IC2") (pin "Y31") (pinfunction "IO_L12N_T1_MRCC_14_Y31") (pintype "bidirectional"))
      (node (ref "R306") (pin "1") (pinfunction "1_1") (pintype "passive"))
      (node (ref "R318") (pin "2") (pinfunction "2_2") (pintype "passive"))
    )
    (net (code "292") (name "Net-(IC2C-IO_L12P_T1_MRCC_14)") (class "Default")
      (node (ref "IC2") (pin "Y30") (pinfunction "IO_L12P_T1_MRCC_14_Y30") (pintype "bidirectional"))
      (node (ref "R318") (pin "1") (pinfunction "1_1") (pintype "passive"))
      (node (ref "R319") (pin "1") (pinfunction "1_1") (pintype "passive"))
    )
    (net (code "293") (name "Net-(IC2C-IO_L13N_T2_MRCC_14)") (class "Default")
      (node (ref "IC2") (pin "AB30") (pinfunction "IO_L13N_T2_MRCC_14_AB30") (pintype "bidirectional"))
      (node (ref "R149") (pin "1") (pinfunction "1_1") (pintype "passive"))
      (node (ref "R150") (pin "2") (pinfunction "2_2") (pintype "passive"))
    )
    (net (code "294") (name "Net-(IC2C-IO_L13P_T2_MRCC_14)") (class "Default")
      (node (ref "IC2") (pin "AA30") (pinfunction "IO_L13P_T2_MRCC_14_AA30") (pintype "bidirectional"))
      (node (ref "R150") (pin "1") (pinfunction "1_1") (pintype "passive"))
      (node (ref "R300") (pin "1") (pinfunction "1_1") (pintype "passive"))
    )
    (net (code "295") (name "PVADJ2") (class "Default")
      (node (ref "R123") (pin "1") (pinfunction "1_1") (pintype "passive"))
      (node (ref "R270") (pin "1") (pinfunction "1_1") (pintype "passive"))
      (node (ref "R323") (pin "1") (pinfunction "1_1") (pintype "passive"))
    )
    (net (code "296") (name "unconnected-(IC2B-IO_L12N_T1_MRCC_13-PadAG30)") (class "Default")
      (node (ref "IC2") (pin "AG30") (pinfunction "IO_L12N_T1_MRCC_13_AG30") (pintype "bidirectional"))
    )
    (net (code "297") (name "unconnected-(IC2B-IO_L12P_T1_MRCC_13-PadAG29)") (class "Default")
      (node (ref "IC2") (pin "AG29") (pinfunction "IO_L12P_T1_MRCC_13_AG29") (pintype "bidirectional"))
    )
    (net (code "298") (name "unconnected-(IC2B-IO_L13N_T2_MRCC_13-PadAH29)") (class "Default")
      (node (ref "IC2") (pin "AH29") (pinfunction "IO_L13N_T2_MRCC_13_AH29") (pintype "bidirectional"))
    )
    (net (code "299") (name "unconnected-(IC2B-IO_L13P_T2_MRCC_13-PadAH28)") (class "Default")
      (node (ref "IC2") (pin "AH28") (pinfunction "IO_L13P_T2_MRCC_13_AH28") (pintype "bidirectional"))
    )
    (net (code "300") (name "unconnected-(IC2C-IO_L3N_T0_DQS_EMCCLK_14-PadY26)") (class "Default")
      (node (ref "IC2") (pin "Y26") (pinfunction "IO_L3N_T0_DQS_EMCCLK_14_Y26") (pintype "bidirectional"))
    )
    (net (code "301") (name "unconnected-(IC2C-IO_L19P_T3_A10_D26_14-PadAC28)") (class "Default")
      (node (ref "IC2") (pin "AC28") (pinfunction "IO_L19P_T3_A10_D26_14_AC28") (pintype "bidirectional"))
    )
    (net (code "302") (name "unconnected-(IC2D-IO_L6P_T0_15-PadR25)") (class "Default")
      (node (ref "IC2") (pin "R25") (pinfunction "IO_L6P_T0_15_R25") (pintype "bidirectional"))
    )
    (net (code "303") (name "unconnected-(IC2D-IO_L19P_T3_A22_15-PadT32)") (class "Default")
      (node (ref "IC2") (pin "T32") (pinfunction "IO_L19P_T3_A22_15_T32") (pintype "bidirectional"))
    )
    (net (code "304") (name "unconnected-(R540-Pad1)") (class "Default")
      (node (ref "R540") (pin "1") (pinfunction "1_1") (pintype "passive"))
    )
    (net (code "305") (name "unconnected-(R542-Pad1)") (class "Default")
      (node (ref "R542") (pin "1") (pinfunction "1_1") (pintype "passive"))
    )
  )
)
